# SW.net
KiCad netlist of a schematic drawn in Altium Designer
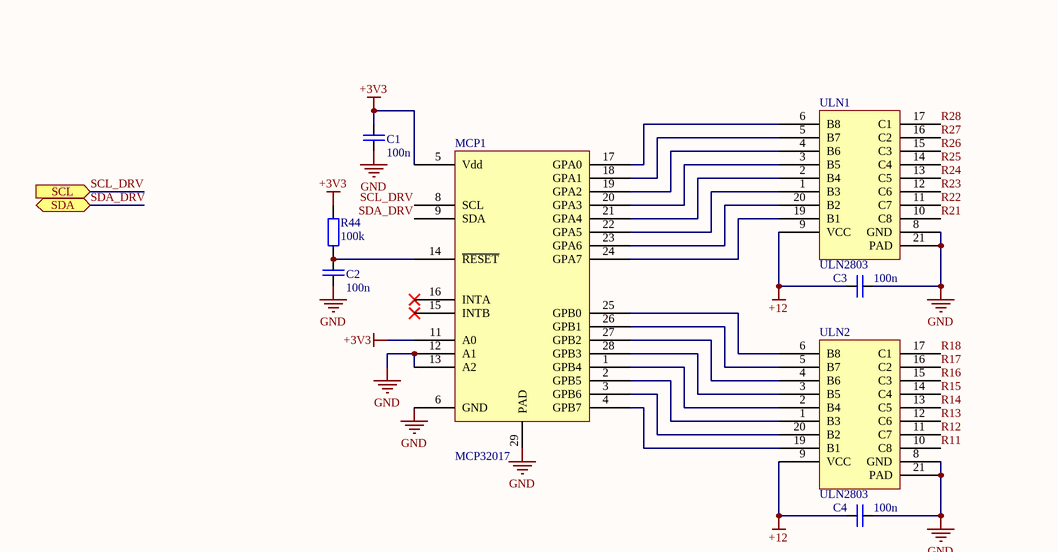
[diagram p0: SW.SchDoc, top left]
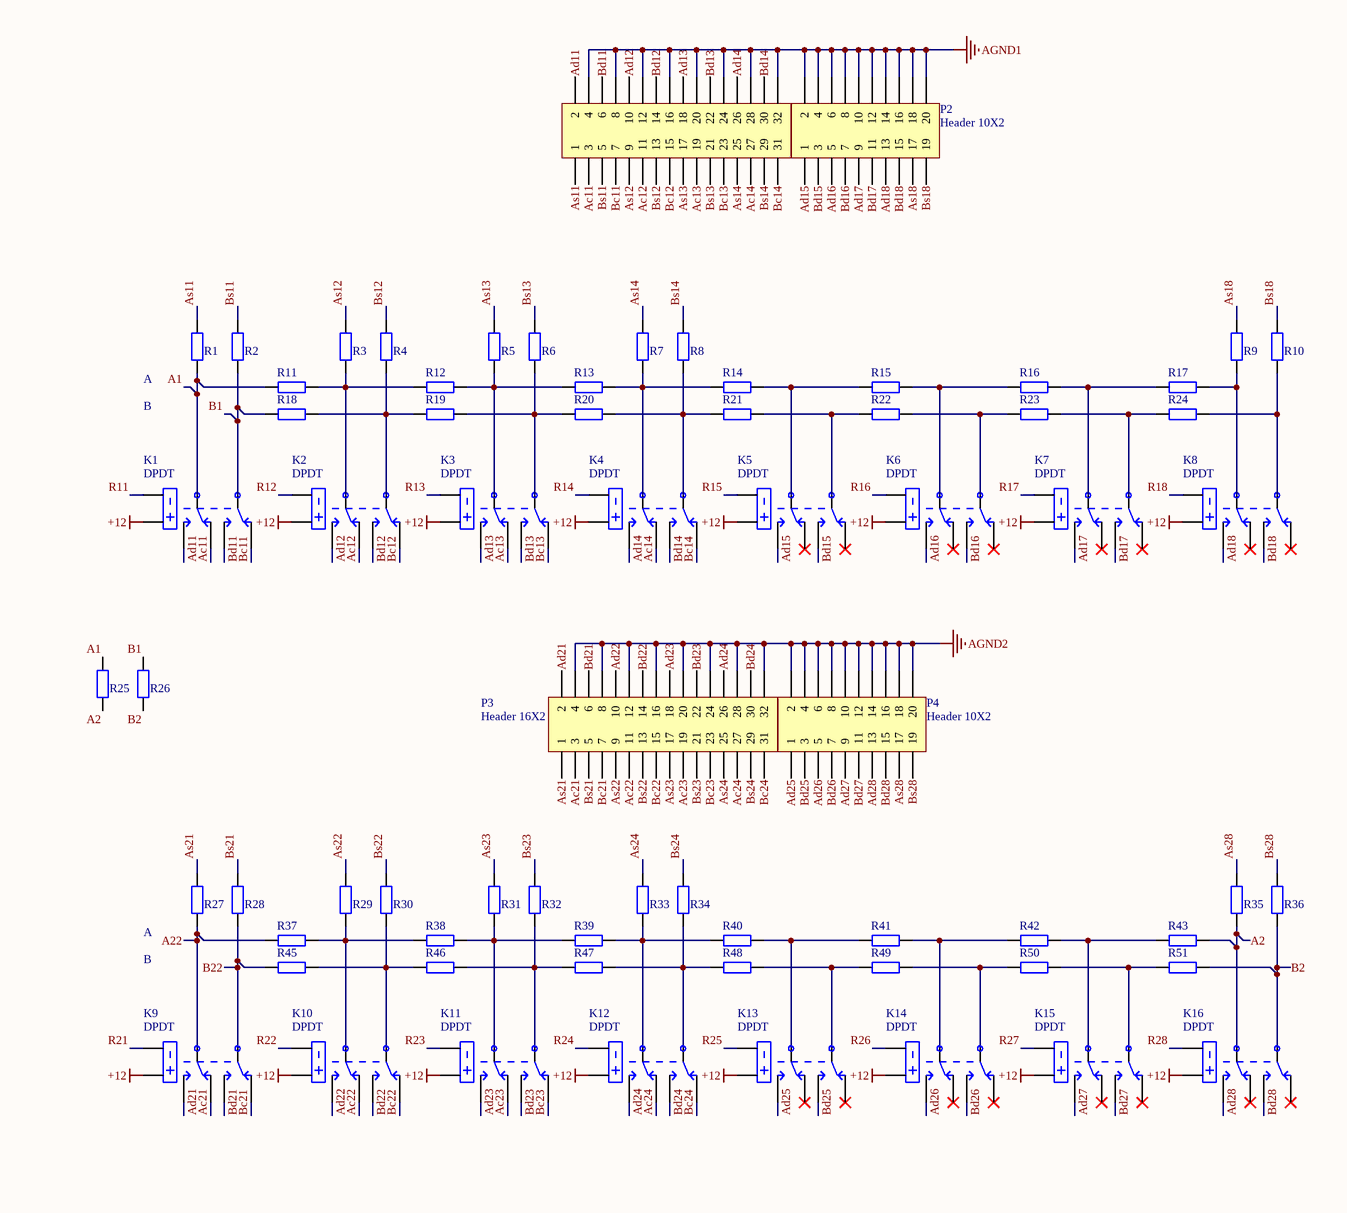
[diagram p1: SW.SchDoc, top right]
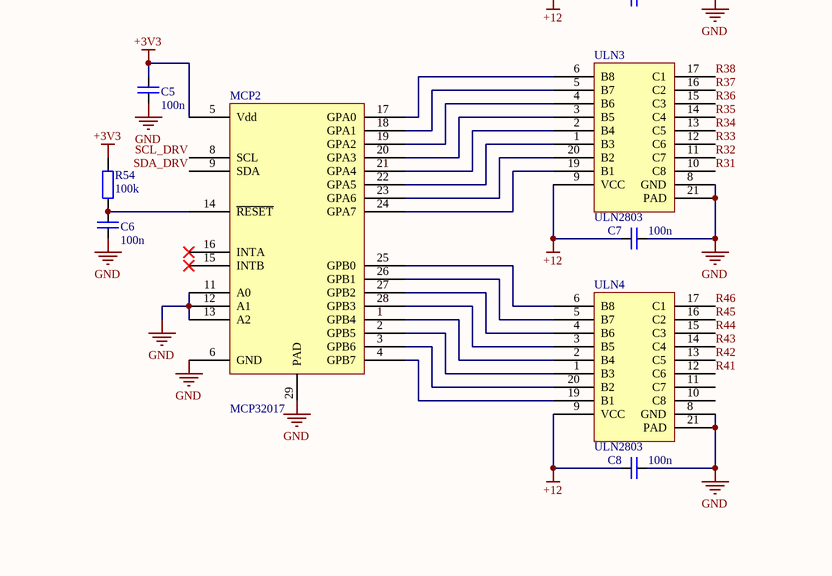
[diagram p2: SW.SchDoc, bottom left]
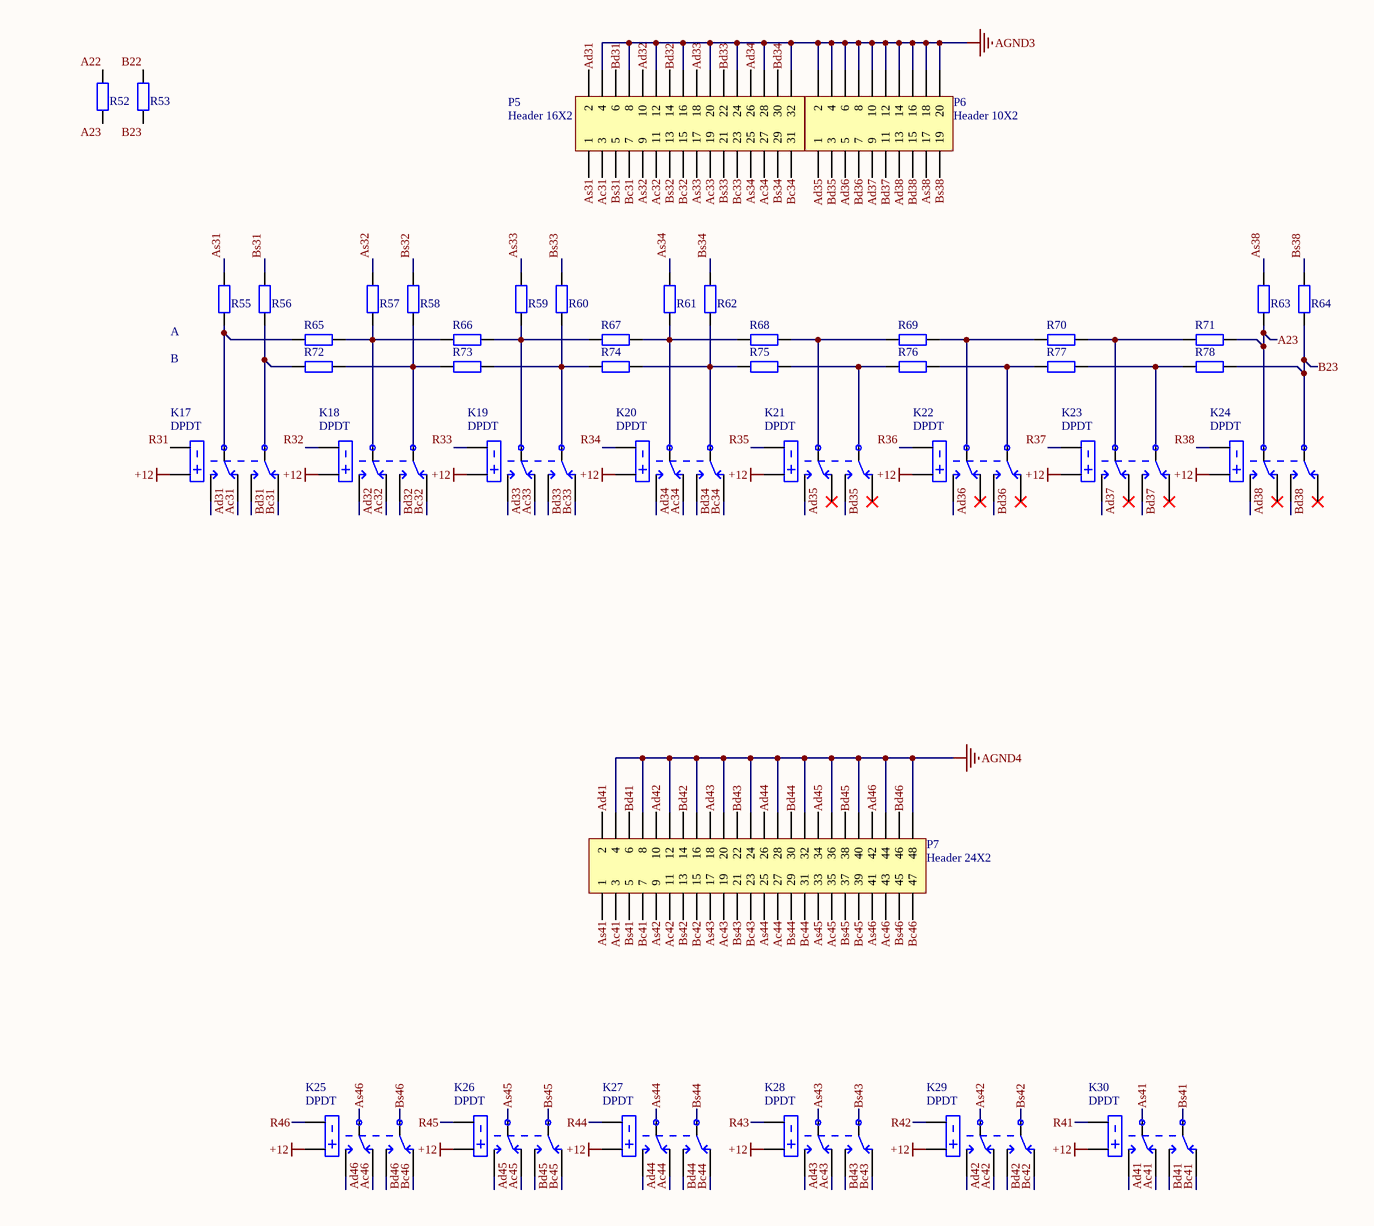
[diagram p3: SW.SchDoc, bottom right]

(export (version "E")
  (design (tool "Eeschema 10.0.6"))
  (components
    (comp (ref "C1")
      (value "100n")
      (footprint "R1005_0402i_L")
      (description "Capacitor")
      (libsource (lib "General") (part "C"))
    )
    (comp (ref "C2")
      (value "100n")
      (footprint "R1005_0402i_L")
      (description "Capacitor")
      (libsource (lib "General") (part "C"))
    )
    (comp (ref "C3")
      (value "100n")
      (footprint "R1005_0402i_L")
      (description "Capacitor")
      (libsource (lib "General") (part "C"))
    )
    (comp (ref "C4")
      (value "100n")
      (footprint "R1005_0402i_L")
      (description "Capacitor")
      (libsource (lib "General") (part "C"))
    )
    (comp (ref "C5")
      (value "100n")
      (footprint "R1005_0402i_L")
      (description "Capacitor")
      (libsource (lib "General") (part "C"))
    )
    (comp (ref "C6")
      (value "100n")
      (footprint "R1005_0402i_L")
      (description "Capacitor")
      (libsource (lib "General") (part "C"))
    )
    (comp (ref "C7")
      (value "100n")
      (footprint "R1005_0402i_L")
      (description "Capacitor")
      (libsource (lib "General") (part "C"))
    )
    (comp (ref "C8")
      (value "100n")
      (footprint "R1005_0402i_L")
      (description "Capacitor")
      (libsource (lib "General") (part "C"))
    )
    (comp (ref "K1")
      (value "DPDT")
      (footprint "AXICOM IM-G Relay")
      (description "TE CONNECTIVITY  IM-GR  RELAY, DPDT, NO")
      (libsource (lib "components_library") (part "IM-GR Relay DPDT"))
    )
    (comp (ref "K2")
      (value "DPDT")
      (footprint "AXICOM IM-G Relay")
      (description "TE CONNECTIVITY  IM-GR  RELAY, DPDT, NO")
      (libsource (lib "components_library") (part "IM-GR Relay DPDT"))
    )
    (comp (ref "K3")
      (value "DPDT")
      (footprint "AXICOM IM-G Relay")
      (description "TE CONNECTIVITY  IM-GR  RELAY, DPDT, NO")
      (libsource (lib "components_library") (part "IM-GR Relay DPDT"))
    )
    (comp (ref "K4")
      (value "DPDT")
      (footprint "AXICOM IM-G Relay")
      (description "TE CONNECTIVITY  IM-GR  RELAY, DPDT, NO")
      (libsource (lib "components_library") (part "IM-GR Relay DPDT"))
    )
    (comp (ref "K5")
      (value "DPDT")
      (footprint "AXICOM IM-G Relay")
      (description "TE CONNECTIVITY  IM-GR  RELAY, DPDT, NO")
      (libsource (lib "components_library") (part "IM-GR Relay DPDT"))
    )
    (comp (ref "K6")
      (value "DPDT")
      (footprint "AXICOM IM-G Relay")
      (description "TE CONNECTIVITY  IM-GR  RELAY, DPDT, NO")
      (libsource (lib "components_library") (part "IM-GR Relay DPDT"))
    )
    (comp (ref "K7")
      (value "DPDT")
      (footprint "AXICOM IM-G Relay")
      (description "TE CONNECTIVITY  IM-GR  RELAY, DPDT, NO")
      (libsource (lib "components_library") (part "IM-GR Relay DPDT"))
    )
    (comp (ref "K8")
      (value "DPDT")
      (footprint "AXICOM IM-G Relay")
      (description "TE CONNECTIVITY  IM-GR  RELAY, DPDT, NO")
      (libsource (lib "components_library") (part "IM-GR Relay DPDT"))
    )
    (comp (ref "K9")
      (value "DPDT")
      (footprint "AXICOM IM-G Relay")
      (description "TE CONNECTIVITY  IM-GR  RELAY, DPDT, NO")
      (libsource (lib "components_library") (part "IM-GR Relay DPDT"))
    )
    (comp (ref "K10")
      (value "DPDT")
      (footprint "AXICOM IM-G Relay")
      (description "TE CONNECTIVITY  IM-GR  RELAY, DPDT, NO")
      (libsource (lib "components_library") (part "IM-GR Relay DPDT"))
    )
    (comp (ref "K11")
      (value "DPDT")
      (footprint "AXICOM IM-G Relay")
      (description "TE CONNECTIVITY  IM-GR  RELAY, DPDT, NO")
      (libsource (lib "components_library") (part "IM-GR Relay DPDT"))
    )
    (comp (ref "K12")
      (value "DPDT")
      (footprint "AXICOM IM-G Relay")
      (description "TE CONNECTIVITY  IM-GR  RELAY, DPDT, NO")
      (libsource (lib "components_library") (part "IM-GR Relay DPDT"))
    )
    (comp (ref "K13")
      (value "DPDT")
      (footprint "AXICOM IM-G Relay")
      (description "TE CONNECTIVITY  IM-GR  RELAY, DPDT, NO")
      (libsource (lib "components_library") (part "IM-GR Relay DPDT"))
    )
    (comp (ref "K14")
      (value "DPDT")
      (footprint "AXICOM IM-G Relay")
      (description "TE CONNECTIVITY  IM-GR  RELAY, DPDT, NO")
      (libsource (lib "components_library") (part "IM-GR Relay DPDT"))
    )
    (comp (ref "K15")
      (value "DPDT")
      (footprint "AXICOM IM-G Relay")
      (description "TE CONNECTIVITY  IM-GR  RELAY, DPDT, NO")
      (libsource (lib "components_library") (part "IM-GR Relay DPDT"))
    )
    (comp (ref "K16")
      (value "DPDT")
      (footprint "AXICOM IM-G Relay")
      (description "TE CONNECTIVITY  IM-GR  RELAY, DPDT, NO")
      (libsource (lib "components_library") (part "IM-GR Relay DPDT"))
    )
    (comp (ref "K17")
      (value "DPDT")
      (footprint "AXICOM IM-G Relay")
      (description "TE CONNECTIVITY  IM-GR  RELAY, DPDT, NO")
      (libsource (lib "components_library") (part "IM-GR Relay DPDT"))
    )
    (comp (ref "K18")
      (value "DPDT")
      (footprint "AXICOM IM-G Relay")
      (description "TE CONNECTIVITY  IM-GR  RELAY, DPDT, NO")
      (libsource (lib "components_library") (part "IM-GR Relay DPDT"))
    )
    (comp (ref "K19")
      (value "DPDT")
      (footprint "AXICOM IM-G Relay")
      (description "TE CONNECTIVITY  IM-GR  RELAY, DPDT, NO")
      (libsource (lib "components_library") (part "IM-GR Relay DPDT"))
    )
    (comp (ref "K20")
      (value "DPDT")
      (footprint "AXICOM IM-G Relay")
      (description "TE CONNECTIVITY  IM-GR  RELAY, DPDT, NO")
      (libsource (lib "components_library") (part "IM-GR Relay DPDT"))
    )
    (comp (ref "K21")
      (value "DPDT")
      (footprint "AXICOM IM-G Relay")
      (description "TE CONNECTIVITY  IM-GR  RELAY, DPDT, NO")
      (libsource (lib "components_library") (part "IM-GR Relay DPDT"))
    )
    (comp (ref "K22")
      (value "DPDT")
      (footprint "AXICOM IM-G Relay")
      (description "TE CONNECTIVITY  IM-GR  RELAY, DPDT, NO")
      (libsource (lib "components_library") (part "IM-GR Relay DPDT"))
    )
    (comp (ref "K23")
      (value "DPDT")
      (footprint "AXICOM IM-G Relay")
      (description "TE CONNECTIVITY  IM-GR  RELAY, DPDT, NO")
      (libsource (lib "components_library") (part "IM-GR Relay DPDT"))
    )
    (comp (ref "K24")
      (value "DPDT")
      (footprint "AXICOM IM-G Relay")
      (description "TE CONNECTIVITY  IM-GR  RELAY, DPDT, NO")
      (libsource (lib "components_library") (part "IM-GR Relay DPDT"))
    )
    (comp (ref "K25")
      (value "DPDT")
      (footprint "AXICOM IM-G Relay")
      (description "TE CONNECTIVITY  IM-GR  RELAY, DPDT, NO")
      (libsource (lib "components_library") (part "IM-GR Relay DPDT"))
    )
    (comp (ref "K26")
      (value "DPDT")
      (footprint "AXICOM IM-G Relay")
      (description "TE CONNECTIVITY  IM-GR  RELAY, DPDT, NO")
      (libsource (lib "components_library") (part "IM-GR Relay DPDT"))
    )
    (comp (ref "K27")
      (value "DPDT")
      (footprint "AXICOM IM-G Relay")
      (description "TE CONNECTIVITY  IM-GR  RELAY, DPDT, NO")
      (libsource (lib "components_library") (part "IM-GR Relay DPDT"))
    )
    (comp (ref "K28")
      (value "DPDT")
      (footprint "AXICOM IM-G Relay")
      (description "TE CONNECTIVITY  IM-GR  RELAY, DPDT, NO")
      (libsource (lib "components_library") (part "IM-GR Relay DPDT"))
    )
    (comp (ref "K29")
      (value "DPDT")
      (footprint "AXICOM IM-G Relay")
      (description "TE CONNECTIVITY  IM-GR  RELAY, DPDT, NO")
      (libsource (lib "components_library") (part "IM-GR Relay DPDT"))
    )
    (comp (ref "K30")
      (value "DPDT")
      (footprint "AXICOM IM-G Relay")
      (description "TE CONNECTIVITY  IM-GR  RELAY, DPDT, NO")
      (libsource (lib "components_library") (part "IM-GR Relay DPDT"))
    )
    (comp (ref "MCP1")
      (value "MCP32017")
      (footprint "MCP23017 QFN")
      (libsource (lib "components_library") (part "MCP32017"))
    )
    (comp (ref "MCP2")
      (value "MCP32017")
      (footprint "MCP23017 QFN")
      (libsource (lib "components_library") (part "MCP32017"))
    )
    (comp (ref "P1")
      (value "Header 16X2")
      (footprint "HDR2X16")
      (description "Header, 16-Pin, Dual row")
      (fields (field (name "PUBLISHER") "Altium Limited"))
      (libsource (lib "Miscellaneous Connectors") (part "Header 16X2"))
    )
    (comp (ref "P2")
      (value "Header 10X2")
      (footprint "HDR2X10")
      (description "Header, 10-Pin, Dual row")
      (fields (field (name "PUBLISHER") "Altium Limited"))
      (libsource (lib "Miscellaneous Connectors") (part "Header 10X2"))
    )
    (comp (ref "P3")
      (value "Header 16X2")
      (footprint "HDR2X16")
      (description "Header, 16-Pin, Dual row")
      (fields (field (name "PUBLISHER") "Altium Limited"))
      (libsource (lib "Miscellaneous Connectors") (part "Header 16X2"))
    )
    (comp (ref "P4")
      (value "Header 10X2")
      (footprint "HDR2X10")
      (description "Header, 10-Pin, Dual row")
      (fields (field (name "PUBLISHER") "Altium Limited"))
      (libsource (lib "Miscellaneous Connectors") (part "Header 10X2"))
    )
    (comp (ref "P5")
      (value "Header 16X2")
      (footprint "HDR2X16")
      (description "Header, 16-Pin, Dual row")
      (fields (field (name "PUBLISHER") "Altium Limited"))
      (libsource (lib "Miscellaneous Connectors") (part "Header 16X2"))
    )
    (comp (ref "P6")
      (value "Header 10X2")
      (footprint "HDR2X10")
      (description "Header, 10-Pin, Dual row")
      (fields (field (name "PUBLISHER") "Altium Limited"))
      (libsource (lib "Miscellaneous Connectors") (part "Header 10X2"))
    )
    (comp (ref "P7")
      (value "Header 24X2")
      (footprint "HDR2X24")
      (description "Header, 24-Pin, Dual row")
      (fields (field (name "PUBLISHER") "Altium Limited"))
      (libsource (lib "Miscellaneous Connectors") (part "Header 24X2"))
    )
    (comp (ref "R1") (value "R") (footprint "R1608_0603I_L") (libsource (lib "General") (part "R")))
    (comp (ref "R2") (value "R") (footprint "R1608_0603I_L") (libsource (lib "General") (part "R")))
    (comp (ref "R3") (value "R") (footprint "R1608_0603I_L") (libsource (lib "General") (part "R")))
    (comp (ref "R4") (value "R") (footprint "R1608_0603I_L") (libsource (lib "General") (part "R")))
    (comp (ref "R5") (value "R") (footprint "R1608_0603I_L") (libsource (lib "General") (part "R")))
    (comp (ref "R6") (value "R") (footprint "R1608_0603I_L") (libsource (lib "General") (part "R")))
    (comp (ref "R7") (value "R") (footprint "R1608_0603I_L") (libsource (lib "General") (part "R")))
    (comp (ref "R8") (value "R") (footprint "R1608_0603I_L") (libsource (lib "General") (part "R")))
    (comp (ref "R9") (value "R") (footprint "R1608_0603I_L") (libsource (lib "General") (part "R")))
    (comp (ref "R10") (value "R") (footprint "R1608_0603I_L") (libsource (lib "General") (part "R")))
    (comp (ref "R11") (value "R") (footprint "R1608_0603I_L") (libsource (lib "General") (part "R")))
    (comp (ref "R12") (value "R") (footprint "R1608_0603I_L") (libsource (lib "General") (part "R")))
    (comp (ref "R13") (value "R") (footprint "R1608_0603I_L") (libsource (lib "General") (part "R")))
    (comp (ref "R14") (value "R") (footprint "R1608_0603I_L") (libsource (lib "General") (part "R")))
    (comp (ref "R15") (value "R") (footprint "R1608_0603I_L") (libsource (lib "General") (part "R")))
    (comp (ref "R16") (value "R") (footprint "R1608_0603I_L") (libsource (lib "General") (part "R")))
    (comp (ref "R17") (value "R") (footprint "R1608_0603I_L") (libsource (lib "General") (part "R")))
    (comp (ref "R18") (value "R") (footprint "R1608_0603I_L") (libsource (lib "General") (part "R")))
    (comp (ref "R19") (value "R") (footprint "R1608_0603I_L") (libsource (lib "General") (part "R")))
    (comp (ref "R20") (value "R") (footprint "R1608_0603I_L") (libsource (lib "General") (part "R")))
    (comp (ref "R21") (value "R") (footprint "R1608_0603I_L") (libsource (lib "General") (part "R")))
    (comp (ref "R22") (value "R") (footprint "R1608_0603I_L") (libsource (lib "General") (part "R")))
    (comp (ref "R23") (value "R") (footprint "R1608_0603I_L") (libsource (lib "General") (part "R")))
    (comp (ref "R24") (value "R") (footprint "R1608_0603I_L") (libsource (lib "General") (part "R")))
    (comp (ref "R25") (value "R") (footprint "R1608_0603I_L") (libsource (lib "General") (part "R")))
    (comp (ref "R26") (value "R") (footprint "R1608_0603I_L") (libsource (lib "General") (part "R")))
    (comp (ref "R27") (value "R") (footprint "R1608_0603I_L") (libsource (lib "General") (part "R")))
    (comp (ref "R28") (value "R") (footprint "R1608_0603I_L") (libsource (lib "General") (part "R")))
    (comp (ref "R29") (value "R") (footprint "R1608_0603I_L") (libsource (lib "General") (part "R")))
    (comp (ref "R30") (value "R") (footprint "R1608_0603I_L") (libsource (lib "General") (part "R")))
    (comp (ref "R31") (value "R") (footprint "R1608_0603I_L") (libsource (lib "General") (part "R")))
    (comp (ref "R32") (value "R") (footprint "R1608_0603I_L") (libsource (lib "General") (part "R")))
    (comp (ref "R33") (value "R") (footprint "R1608_0603I_L") (libsource (lib "General") (part "R")))
    (comp (ref "R34") (value "R") (footprint "R1608_0603I_L") (libsource (lib "General") (part "R")))
    (comp (ref "R35") (value "R") (footprint "R1608_0603I_L") (libsource (lib "General") (part "R")))
    (comp (ref "R36") (value "R") (footprint "R1608_0603I_L") (libsource (lib "General") (part "R")))
    (comp (ref "R37") (value "R") (footprint "R1608_0603I_L") (libsource (lib "General") (part "R")))
    (comp (ref "R38") (value "R") (footprint "R1608_0603I_L") (libsource (lib "General") (part "R")))
    (comp (ref "R39") (value "R") (footprint "R1608_0603I_L") (libsource (lib "General") (part "R")))
    (comp (ref "R40") (value "R") (footprint "R1608_0603I_L") (libsource (lib "General") (part "R")))
    (comp (ref "R41") (value "R") (footprint "R1608_0603I_L") (libsource (lib "General") (part "R")))
    (comp (ref "R42") (value "R") (footprint "R1608_0603I_L") (libsource (lib "General") (part "R")))
    (comp (ref "R43") (value "R") (footprint "R1608_0603I_L") (libsource (lib "General") (part "R")))
    (comp (ref "R44")
      (value "100k")
      (footprint "R1005_0402i_L")
      (description "R")
      (libsource (lib "General") (part "R"))
    )
    (comp (ref "R45") (value "R") (footprint "R1608_0603I_L") (libsource (lib "General") (part "R")))
    (comp (ref "R46") (value "R") (footprint "R1608_0603I_L") (libsource (lib "General") (part "R")))
    (comp (ref "R47") (value "R") (footprint "R1608_0603I_L") (libsource (lib "General") (part "R")))
    (comp (ref "R48") (value "R") (footprint "R1608_0603I_L") (libsource (lib "General") (part "R")))
    (comp (ref "R49") (value "R") (footprint "R1608_0603I_L") (libsource (lib "General") (part "R")))
    (comp (ref "R50") (value "R") (footprint "R1608_0603I_L") (libsource (lib "General") (part "R")))
    (comp (ref "R51") (value "R") (footprint "R1608_0603I_L") (libsource (lib "General") (part "R")))
    (comp (ref "R52") (value "R") (footprint "R1608_0603I_L") (libsource (lib "General") (part "R")))
    (comp (ref "R53") (value "R") (footprint "R1608_0603I_L") (libsource (lib "General") (part "R")))
    (comp (ref "R54")
      (value "100k")
      (footprint "R1005_0402i_L")
      (description "R")
      (libsource (lib "General") (part "R"))
    )
    (comp (ref "R55") (value "R") (footprint "R1608_0603I_L") (libsource (lib "General") (part "R")))
    (comp (ref "R56") (value "R") (footprint "R1608_0603I_L") (libsource (lib "General") (part "R")))
    (comp (ref "R57") (value "R") (footprint "R1608_0603I_L") (libsource (lib "General") (part "R")))
    (comp (ref "R58") (value "R") (footprint "R1608_0603I_L") (libsource (lib "General") (part "R")))
    (comp (ref "R59") (value "R") (footprint "R1608_0603I_L") (libsource (lib "General") (part "R")))
    (comp (ref "R60") (value "R") (footprint "R1608_0603I_L") (libsource (lib "General") (part "R")))
    (comp (ref "R61") (value "R") (footprint "R1608_0603I_L") (libsource (lib "General") (part "R")))
    (comp (ref "R62") (value "R") (footprint "R1608_0603I_L") (libsource (lib "General") (part "R")))
    (comp (ref "R63") (value "R") (footprint "R1608_0603I_L") (libsource (lib "General") (part "R")))
    (comp (ref "R64") (value "R") (footprint "R1608_0603I_L") (libsource (lib "General") (part "R")))
    (comp (ref "R65") (value "R") (footprint "R1608_0603I_L") (libsource (lib "General") (part "R")))
    (comp (ref "R66") (value "R") (footprint "R1608_0603I_L") (libsource (lib "General") (part "R")))
    (comp (ref "R67") (value "R") (footprint "R1608_0603I_L") (libsource (lib "General") (part "R")))
    (comp (ref "R68") (value "R") (footprint "R1608_0603I_L") (libsource (lib "General") (part "R")))
    (comp (ref "R69") (value "R") (footprint "R1608_0603I_L") (libsource (lib "General") (part "R")))
    (comp (ref "R70") (value "R") (footprint "R1608_0603I_L") (libsource (lib "General") (part "R")))
    (comp (ref "R71") (value "R") (footprint "R1608_0603I_L") (libsource (lib "General") (part "R")))
    (comp (ref "R72") (value "R") (footprint "R1608_0603I_L") (libsource (lib "General") (part "R")))
    (comp (ref "R73") (value "R") (footprint "R1608_0603I_L") (libsource (lib "General") (part "R")))
    (comp (ref "R74") (value "R") (footprint "R1608_0603I_L") (libsource (lib "General") (part "R")))
    (comp (ref "R75") (value "R") (footprint "R1608_0603I_L") (libsource (lib "General") (part "R")))
    (comp (ref "R76") (value "R") (footprint "R1608_0603I_L") (libsource (lib "General") (part "R")))
    (comp (ref "R77") (value "R") (footprint "R1608_0603I_L") (libsource (lib "General") (part "R")))
    (comp (ref "R78") (value "R") (footprint "R1608_0603I_L") (libsource (lib "General") (part "R")))
    (comp (ref "ULN1")
      (value "ULN2803")
      (footprint "QFN127P600-8N")
      (libsource (lib "Schlib1") (part "ULN2803"))
    )
    (comp (ref "ULN2")
      (value "ULN2803")
      (footprint "QFN127P600-8N")
      (libsource (lib "Schlib1") (part "ULN2803"))
    )
    (comp (ref "ULN3")
      (value "ULN2803")
      (footprint "QFN127P600-8N")
      (libsource (lib "Schlib1") (part "ULN2803"))
    )
    (comp (ref "ULN4")
      (value "ULN2803")
      (footprint "QFN127P600-8N")
      (libsource (lib "Schlib1") (part "ULN2803"))
    )
  )
  (nets
    (net (code "1") (name "+3V3") (class "Default")
      (node (ref "C1") (pin "2") (pinfunction "2_2") (pintype "passive"))
      (node (ref "C5") (pin "2") (pinfunction "2_2") (pintype "passive"))
      (node (ref "MCP1") (pin "11") (pinfunction "A0_11") (pintype "passive"))
      (node (ref "MCP1") (pin "5") (pinfunction "Vdd_5") (pintype "passive"))
      (node (ref "MCP2") (pin "5") (pinfunction "Vdd_5") (pintype "passive"))
      (node (ref "R44") (pin "1") (pintype "passive"))
      (node (ref "R54") (pin "1") (pintype "passive"))
    )
    (net (code "2") (name "+12") (class "Default")
      (node (ref "C3") (pin "1") (pinfunction "1_1") (pintype "passive"))
      (node (ref "C4") (pin "1") (pinfunction "1_1") (pintype "passive"))
      (node (ref "C7") (pin "1") (pinfunction "1_1") (pintype "passive"))
      (node (ref "C8") (pin "1") (pinfunction "1_1") (pintype "passive"))
      (node (ref "K1") (pin "1") (pinfunction "1_1") (pintype "passive"))
      (node (ref "K10") (pin "1") (pinfunction "1_1") (pintype "passive"))
      (node (ref "K11") (pin "1") (pinfunction "1_1") (pintype "passive"))
      (node (ref "K12") (pin "1") (pinfunction "1_1") (pintype "passive"))
      (node (ref "K13") (pin "1") (pinfunction "1_1") (pintype "passive"))
      (node (ref "K14") (pin "1") (pinfunction "1_1") (pintype "passive"))
      (node (ref "K15") (pin "1") (pinfunction "1_1") (pintype "passive"))
      (node (ref "K16") (pin "1") (pinfunction "1_1") (pintype "passive"))
      (node (ref "K17") (pin "1") (pinfunction "1_1") (pintype "passive"))
      (node (ref "K18") (pin "1") (pinfunction "1_1") (pintype "passive"))
      (node (ref "K19") (pin "1") (pinfunction "1_1") (pintype "passive"))
      (node (ref "K2") (pin "1") (pinfunction "1_1") (pintype "passive"))
      (node (ref "K20") (pin "1") (pinfunction "1_1") (pintype "passive"))
      (node (ref "K21") (pin "1") (pinfunction "1_1") (pintype "passive"))
      (node (ref "K22") (pin "1") (pinfunction "1_1") (pintype "passive"))
      (node (ref "K23") (pin "1") (pinfunction "1_1") (pintype "passive"))
      (node (ref "K24") (pin "1") (pinfunction "1_1") (pintype "passive"))
      (node (ref "K25") (pin "1") (pinfunction "1_1") (pintype "passive"))
      (node (ref "K26") (pin "1") (pinfunction "1_1") (pintype "passive"))
      (node (ref "K27") (pin "1") (pinfunction "1_1") (pintype "passive"))
      (node (ref "K28") (pin "1") (pinfunction "1_1") (pintype "passive"))
      (node (ref "K29") (pin "1") (pinfunction "1_1") (pintype "passive"))
      (node (ref "K3") (pin "1") (pinfunction "1_1") (pintype "passive"))
      (node (ref "K30") (pin "1") (pinfunction "1_1") (pintype "passive"))
      (node (ref "K4") (pin "1") (pinfunction "1_1") (pintype "passive"))
      (node (ref "K5") (pin "1") (pinfunction "1_1") (pintype "passive"))
      (node (ref "K6") (pin "1") (pinfunction "1_1") (pintype "passive"))
      (node (ref "K7") (pin "1") (pinfunction "1_1") (pintype "passive"))
      (node (ref "K8") (pin "1") (pinfunction "1_1") (pintype "passive"))
      (node (ref "K9") (pin "1") (pinfunction "1_1") (pintype "passive"))
      (node (ref "ULN1") (pin "9") (pinfunction "VCC_9") (pintype "passive"))
      (node (ref "ULN2") (pin "9") (pinfunction "VCC_9") (pintype "passive"))
      (node (ref "ULN3") (pin "9") (pinfunction "VCC_9") (pintype "passive"))
      (node (ref "ULN4") (pin "9") (pinfunction "VCC_9") (pintype "passive"))
    )
    (net (code "3") (name "/A1") (class "Default")
      (node (ref "K1") (pin "3") (pinfunction "3_3") (pintype "passive"))
      (node (ref "R1") (pin "1") (pintype "passive"))
      (node (ref "R11") (pin "1") (pintype "passive"))
      (node (ref "R25") (pin "2") (pintype "passive"))
    )
    (net (code "4") (name "/A2") (class "Default")
      (node (ref "K16") (pin "3") (pinfunction "3_3") (pintype "passive"))
      (node (ref "R25") (pin "1") (pintype "passive"))
      (node (ref "R35") (pin "1") (pintype "passive"))
      (node (ref "R43") (pin "2") (pintype "passive"))
    )
    (net (code "5") (name "/A22") (class "Default")
      (node (ref "K9") (pin "3") (pinfunction "3_3") (pintype "passive"))
      (node (ref "R27") (pin "1") (pintype "passive"))
      (node (ref "R37") (pin "1") (pintype "passive"))
      (node (ref "R52") (pin "2") (pintype "passive"))
    )
    (net (code "6") (name "/A23") (class "Default")
      (node (ref "K24") (pin "3") (pinfunction "3_3") (pintype "passive"))
      (node (ref "R52") (pin "1") (pintype "passive"))
      (node (ref "R63") (pin "1") (pintype "passive"))
      (node (ref "R71") (pin "2") (pintype "passive"))
    )
    (net (code "7") (name "/Ac11") (class "Default")
      (node (ref "K1") (pin "2") (pinfunction "2_2") (pintype "passive"))
      (node (ref "P1") (pin "3") (pinfunction "3_3") (pintype "passive"))
    )
    (net (code "8") (name "/Ac12") (class "Default")
      (node (ref "K2") (pin "2") (pinfunction "2_2") (pintype "passive"))
      (node (ref "P1") (pin "11") (pinfunction "11_11") (pintype "passive"))
    )
    (net (code "9") (name "/Ac13") (class "Default")
      (node (ref "K3") (pin "2") (pinfunction "2_2") (pintype "passive"))
      (node (ref "P1") (pin "19") (pinfunction "19_19") (pintype "passive"))
    )
    (net (code "10") (name "/Ac14") (class "Default")
      (node (ref "K4") (pin "2") (pinfunction "2_2") (pintype "passive"))
      (node (ref "P1") (pin "27") (pinfunction "27_27") (pintype "passive"))
    )
    (net (code "11") (name "/Ac21") (class "Default")
      (node (ref "K9") (pin "2") (pinfunction "2_2") (pintype "passive"))
      (node (ref "P3") (pin "3") (pinfunction "3_3") (pintype "passive"))
    )
    (net (code "12") (name "/Ac22") (class "Default")
      (node (ref "K10") (pin "2") (pinfunction "2_2") (pintype "passive"))
      (node (ref "P3") (pin "11") (pinfunction "11_11") (pintype "passive"))
    )
    (net (code "13") (name "/Ac23") (class "Default")
      (node (ref "K11") (pin "2") (pinfunction "2_2") (pintype "passive"))
      (node (ref "P3") (pin "19") (pinfunction "19_19") (pintype "passive"))
    )
    (net (code "14") (name "/Ac24") (class "Default")
      (node (ref "K12") (pin "2") (pinfunction "2_2") (pintype "passive"))
      (node (ref "P3") (pin "27") (pinfunction "27_27") (pintype "passive"))
    )
    (net (code "15") (name "/Ac31") (class "Default")
      (node (ref "K17") (pin "2") (pinfunction "2_2") (pintype "passive"))
      (node (ref "P5") (pin "3") (pinfunction "3_3") (pintype "passive"))
    )
    (net (code "16") (name "/Ac32") (class "Default")
      (node (ref "K18") (pin "2") (pinfunction "2_2") (pintype "passive"))
      (node (ref "P5") (pin "11") (pinfunction "11_11") (pintype "passive"))
    )
    (net (code "17") (name "/Ac33") (class "Default")
      (node (ref "K19") (pin "2") (pinfunction "2_2") (pintype "passive"))
      (node (ref "P5") (pin "19") (pinfunction "19_19") (pintype "passive"))
    )
    (net (code "18") (name "/Ac34") (class "Default")
      (node (ref "K20") (pin "2") (pinfunction "2_2") (pintype "passive"))
      (node (ref "P5") (pin "27") (pinfunction "27_27") (pintype "passive"))
    )
    (net (code "19") (name "/Ac41") (class "Default")
      (node (ref "K30") (pin "2") (pinfunction "2_2") (pintype "passive"))
      (node (ref "P7") (pin "3") (pinfunction "3_3") (pintype "passive"))
    )
    (net (code "20") (name "/Ac42") (class "Default")
      (node (ref "K29") (pin "2") (pinfunction "2_2") (pintype "passive"))
      (node (ref "P7") (pin "11") (pinfunction "11_11") (pintype "passive"))
    )
    (net (code "21") (name "/Ac43") (class "Default")
      (node (ref "K28") (pin "2") (pinfunction "2_2") (pintype "passive"))
      (node (ref "P7") (pin "19") (pinfunction "19_19") (pintype "passive"))
    )
    (net (code "22") (name "/Ac44") (class "Default")
      (node (ref "K27") (pin "2") (pinfunction "2_2") (pintype "passive"))
      (node (ref "P7") (pin "27") (pinfunction "27_27") (pintype "passive"))
    )
    (net (code "23") (name "/Ac45") (class "Default")
      (node (ref "K26") (pin "2") (pinfunction "2_2") (pintype "passive"))
      (node (ref "P7") (pin "35") (pinfunction "35_35") (pintype "passive"))
    )
    (net (code "24") (name "/Ac46") (class "Default")
      (node (ref "K25") (pin "2") (pinfunction "2_2") (pintype "passive"))
      (node (ref "P7") (pin "43") (pinfunction "43_43") (pintype "passive"))
    )
    (net (code "25") (name "/Ad11") (class "Default")
      (node (ref "K1") (pin "4") (pinfunction "4_4") (pintype "passive"))
      (node (ref "P1") (pin "2") (pinfunction "2_2") (pintype "passive"))
    )
    (net (code "26") (name "/Ad12") (class "Default")
      (node (ref "K2") (pin "4") (pinfunction "4_4") (pintype "passive"))
      (node (ref "P1") (pin "10") (pinfunction "10_10") (pintype "passive"))
    )
    (net (code "27") (name "/Ad13") (class "Default")
      (node (ref "K3") (pin "4") (pinfunction "4_4") (pintype "passive"))
      (node (ref "P1") (pin "18") (pinfunction "18_18") (pintype "passive"))
    )
    (net (code "28") (name "/Ad14") (class "Default")
      (node (ref "K4") (pin "4") (pinfunction "4_4") (pintype "passive"))
      (node (ref "P1") (pin "26") (pinfunction "26_26") (pintype "passive"))
    )
    (net (code "29") (name "/Ad15") (class "Default")
      (node (ref "K5") (pin "4") (pinfunction "4_4") (pintype "passive"))
      (node (ref "P2") (pin "1") (pinfunction "1_1") (pintype "passive"))
    )
    (net (code "30") (name "/Ad16") (class "Default")
      (node (ref "K6") (pin "4") (pinfunction "4_4") (pintype "passive"))
      (node (ref "P2") (pin "5") (pinfunction "5_5") (pintype "passive"))
    )
    (net (code "31") (name "/Ad17") (class "Default")
      (node (ref "K7") (pin "4") (pinfunction "4_4") (pintype "passive"))
      (node (ref "P2") (pin "9") (pinfunction "9_9") (pintype "passive"))
    )
    (net (code "32") (name "/Ad18") (class "Default")
      (node (ref "K8") (pin "4") (pinfunction "4_4") (pintype "passive"))
      (node (ref "P2") (pin "13") (pinfunction "13_13") (pintype "passive"))
    )
    (net (code "33") (name "/Ad21") (class "Default")
      (node (ref "K9") (pin "4") (pinfunction "4_4") (pintype "passive"))
      (node (ref "P3") (pin "2") (pinfunction "2_2") (pintype "passive"))
    )
    (net (code "34") (name "/Ad22") (class "Default")
      (node (ref "K10") (pin "4") (pinfunction "4_4") (pintype "passive"))
      (node (ref "P3") (pin "10") (pinfunction "10_10") (pintype "passive"))
    )
    (net (code "35") (name "/Ad23") (class "Default")
      (node (ref "K11") (pin "4") (pinfunction "4_4") (pintype "passive"))
      (node (ref "P3") (pin "18") (pinfunction "18_18") (pintype "passive"))
    )
    (net (code "36") (name "/Ad24") (class "Default")
      (node (ref "K12") (pin "4") (pinfunction "4_4") (pintype "passive"))
      (node (ref "P3") (pin "26") (pinfunction "26_26") (pintype "passive"))
    )
    (net (code "37") (name "/Ad25") (class "Default")
      (node (ref "K13") (pin "4") (pinfunction "4_4") (pintype "passive"))
      (node (ref "P4") (pin "1") (pinfunction "1_1") (pintype "passive"))
    )
    (net (code "38") (name "/Ad26") (class "Default")
      (node (ref "K14") (pin "4") (pinfunction "4_4") (pintype "passive"))
      (node (ref "P4") (pin "5") (pinfunction "5_5") (pintype "passive"))
    )
    (net (code "39") (name "/Ad27") (class "Default")
      (node (ref "K15") (pin "4") (pinfunction "4_4") (pintype "passive"))
      (node (ref "P4") (pin "9") (pinfunction "9_9") (pintype "passive"))
    )
    (net (code "40") (name "/Ad28") (class "Default")
      (node (ref "K16") (pin "4") (pinfunction "4_4") (pintype "passive"))
      (node (ref "P4") (pin "13") (pinfunction "13_13") (pintype "passive"))
    )
    (net (code "41") (name "/Ad31") (class "Default")
      (node (ref "K17") (pin "4") (pinfunction "4_4") (pintype "passive"))
      (node (ref "P5") (pin "2") (pinfunction "2_2") (pintype "passive"))
    )
    (net (code "42") (name "/Ad32") (class "Default")
      (node (ref "K18") (pin "4") (pinfunction "4_4") (pintype "passive"))
      (node (ref "P5") (pin "10") (pinfunction "10_10") (pintype "passive"))
    )
    (net (code "43") (name "/Ad33") (class "Default")
      (node (ref "K19") (pin "4") (pinfunction "4_4") (pintype "passive"))
      (node (ref "P5") (pin "18") (pinfunction "18_18") (pintype "passive"))
    )
    (net (code "44") (name "/Ad34") (class "Default")
      (node (ref "K20") (pin "4") (pinfunction "4_4") (pintype "passive"))
      (node (ref "P5") (pin "26") (pinfunction "26_26") (pintype "passive"))
    )
    (net (code "45") (name "/Ad35") (class "Default")
      (node (ref "K21") (pin "4") (pinfunction "4_4") (pintype "passive"))
      (node (ref "P6") (pin "1") (pinfunction "1_1") (pintype "passive"))
    )
    (net (code "46") (name "/Ad36") (class "Default")
      (node (ref "K22") (pin "4") (pinfunction "4_4") (pintype "passive"))
      (node (ref "P6") (pin "5") (pinfunction "5_5") (pintype "passive"))
    )
    (net (code "47") (name "/Ad37") (class "Default")
      (node (ref "K23") (pin "4") (pinfunction "4_4") (pintype "passive"))
      (node (ref "P6") (pin "9") (pinfunction "9_9") (pintype "passive"))
    )
    (net (code "48") (name "/Ad38") (class "Default")
      (node (ref "K24") (pin "4") (pinfunction "4_4") (pintype "passive"))
      (node (ref "P6") (pin "13") (pinfunction "13_13") (pintype "passive"))
    )
    (net (code "49") (name "/Ad41") (class "Default")
      (node (ref "K30") (pin "4") (pinfunction "4_4") (pintype "passive"))
      (node (ref "P7") (pin "2") (pinfunction "2_2") (pintype "passive"))
    )
    (net (code "50") (name "/Ad42") (class "Default")
      (node (ref "K29") (pin "4") (pinfunction "4_4") (pintype "passive"))
      (node (ref "P7") (pin "10") (pinfunction "10_10") (pintype "passive"))
    )
    (net (code "51") (name "/Ad43") (class "Default")
      (node (ref "K28") (pin "4") (pinfunction "4_4") (pintype "passive"))
      (node (ref "P7") (pin "18") (pinfunction "18_18") (pintype "passive"))
    )
    (net (code "52") (name "/Ad44") (class "Default")
      (node (ref "K27") (pin "4") (pinfunction "4_4") (pintype "passive"))
      (node (ref "P7") (pin "26") (pinfunction "26_26") (pintype "passive"))
    )
    (net (code "53") (name "/Ad45") (class "Default")
      (node (ref "K26") (pin "4") (pinfunction "4_4") (pintype "passive"))
      (node (ref "P7") (pin "34") (pinfunction "34_34") (pintype "passive"))
    )
    (net (code "54") (name "/Ad46") (class "Default")
      (node (ref "K25") (pin "4") (pinfunction "4_4") (pintype "passive"))
      (node (ref "P7") (pin "42") (pinfunction "42_42") (pintype "passive"))
    )
    (net (code "55") (name "/As11") (class "Default")
      (node (ref "P1") (pin "1") (pinfunction "1_1") (pintype "passive"))
      (node (ref "R1") (pin "2") (pintype "passive"))
    )
    (net (code "56") (name "/As12") (class "Default")
      (node (ref "P1") (pin "9") (pinfunction "9_9") (pintype "passive"))
      (node (ref "R3") (pin "2") (pintype "passive"))
    )
    (net (code "57") (name "/As13") (class "Default")
      (node (ref "P1") (pin "17") (pinfunction "17_17") (pintype "passive"))
      (node (ref "R5") (pin "2") (pintype "passive"))
    )
    (net (code "58") (name "/As14") (class "Default")
      (node (ref "P1") (pin "25") (pinfunction "25_25") (pintype "passive"))
      (node (ref "R7") (pin "2") (pintype "passive"))
    )
    (net (code "59") (name "/As18") (class "Default")
      (node (ref "P2") (pin "17") (pinfunction "17_17") (pintype "passive"))
      (node (ref "R9") (pin "2") (pintype "passive"))
    )
    (net (code "60") (name "/As21") (class "Default")
      (node (ref "P3") (pin "1") (pinfunction "1_1") (pintype "passive"))
      (node (ref "R27") (pin "2") (pintype "passive"))
    )
    (net (code "61") (name "/As22") (class "Default")
      (node (ref "P3") (pin "9") (pinfunction "9_9") (pintype "passive"))
      (node (ref "R29") (pin "2") (pintype "passive"))
    )
    (net (code "62") (name "/As23") (class "Default")
      (node (ref "P3") (pin "17") (pinfunction "17_17") (pintype "passive"))
      (node (ref "R31") (pin "2") (pintype "passive"))
    )
    (net (code "63") (name "/As24") (class "Default")
      (node (ref "P3") (pin "25") (pinfunction "25_25") (pintype "passive"))
      (node (ref "R33") (pin "2") (pintype "passive"))
    )
    (net (code "64") (name "/As28") (class "Default")
      (node (ref "P4") (pin "17") (pinfunction "17_17") (pintype "passive"))
      (node (ref "R35") (pin "2") (pintype "passive"))
    )
    (net (code "65") (name "/As31") (class "Default")
      (node (ref "P5") (pin "1") (pinfunction "1_1") (pintype "passive"))
      (node (ref "R55") (pin "2") (pintype "passive"))
    )
    (net (code "66") (name "/As32") (class "Default")
      (node (ref "P5") (pin "9") (pinfunction "9_9") (pintype "passive"))
      (node (ref "R57") (pin "2") (pintype "passive"))
    )
    (net (code "67") (name "/As33") (class "Default")
      (node (ref "P5") (pin "17") (pinfunction "17_17") (pintype "passive"))
      (node (ref "R59") (pin "2") (pintype "passive"))
    )
    (net (code "68") (name "/As34") (class "Default")
      (node (ref "P5") (pin "25") (pinfunction "25_25") (pintype "passive"))
      (node (ref "R61") (pin "2") (pintype "passive"))
    )
    (net (code "69") (name "/As38") (class "Default")
      (node (ref "P6") (pin "17") (pinfunction "17_17") (pintype "passive"))
      (node (ref "R63") (pin "2") (pintype "passive"))
    )
    (net (code "70") (name "/As41") (class "Default")
      (node (ref "K30") (pin "3") (pinfunction "3_3") (pintype "passive"))
      (node (ref "P7") (pin "1") (pinfunction "1_1") (pintype "passive"))
    )
    (net (code "71") (name "/As42") (class "Default")
      (node (ref "K29") (pin "3") (pinfunction "3_3") (pintype "passive"))
      (node (ref "P7") (pin "9") (pinfunction "9_9") (pintype "passive"))
    )
    (net (code "72") (name "/As43") (class "Default")
      (node (ref "K28") (pin "3") (pinfunction "3_3") (pintype "passive"))
      (node (ref "P7") (pin "17") (pinfunction "17_17") (pintype "passive"))
    )
    (net (code "73") (name "/As44") (class "Default")
      (node (ref "K27") (pin "3") (pinfunction "3_3") (pintype "passive"))
      (node (ref "P7") (pin "25") (pinfunction "25_25") (pintype "passive"))
    )
    (net (code "74") (name "/As45") (class "Default")
      (node (ref "K26") (pin "3") (pinfunction "3_3") (pintype "passive"))
      (node (ref "P7") (pin "33") (pinfunction "33_33") (pintype "passive"))
    )
    (net (code "75") (name "/As46") (class "Default")
      (node (ref "K25") (pin "3") (pinfunction "3_3") (pintype "passive"))
      (node (ref "P7") (pin "41") (pinfunction "41_41") (pintype "passive"))
    )
    (net (code "76") (name "/B1") (class "Default")
      (node (ref "K1") (pin "6") (pinfunction "6_6") (pintype "passive"))
      (node (ref "R18") (pin "1") (pintype "passive"))
      (node (ref "R2") (pin "1") (pintype "passive"))
      (node (ref "R26") (pin "2") (pintype "passive"))
    )
    (net (code "77") (name "/B2") (class "Default")
      (node (ref "K16") (pin "6") (pinfunction "6_6") (pintype "passive"))
      (node (ref "R26") (pin "1") (pintype "passive"))
      (node (ref "R36") (pin "1") (pintype "passive"))
      (node (ref "R51") (pin "2") (pintype "passive"))
    )
    (net (code "78") (name "/B22") (class "Default")
      (node (ref "K9") (pin "6") (pinfunction "6_6") (pintype "passive"))
      (node (ref "R28") (pin "1") (pintype "passive"))
      (node (ref "R45") (pin "1") (pintype "passive"))
      (node (ref "R53") (pin "2") (pintype "passive"))
    )
    (net (code "79") (name "/B23") (class "Default")
      (node (ref "K24") (pin "6") (pinfunction "6_6") (pintype "passive"))
      (node (ref "R53") (pin "1") (pintype "passive"))
      (node (ref "R64") (pin "1") (pintype "passive"))
      (node (ref "R78") (pin "2") (pintype "passive"))
    )
    (net (code "80") (name "/Bc11") (class "Default")
      (node (ref "K1") (pin "7") (pinfunction "7_7") (pintype "passive"))
      (node (ref "P1") (pin "7") (pinfunction "7_7") (pintype "passive"))
    )
    (net (code "81") (name "/Bc12") (class "Default")
      (node (ref "K2") (pin "7") (pinfunction "7_7") (pintype "passive"))
      (node (ref "P1") (pin "15") (pinfunction "15_15") (pintype "passive"))
    )
    (net (code "82") (name "/Bc13") (class "Default")
      (node (ref "K3") (pin "7") (pinfunction "7_7") (pintype "passive"))
      (node (ref "P1") (pin "23") (pinfunction "23_23") (pintype "passive"))
    )
    (net (code "83") (name "/Bc14") (class "Default")
      (node (ref "K4") (pin "7") (pinfunction "7_7") (pintype "passive"))
      (node (ref "P1") (pin "31") (pinfunction "31_31") (pintype "passive"))
    )
    (net (code "84") (name "/Bc21") (class "Default")
      (node (ref "K9") (pin "7") (pinfunction "7_7") (pintype "passive"))
      (node (ref "P3") (pin "7") (pinfunction "7_7") (pintype "passive"))
    )
    (net (code "85") (name "/Bc22") (class "Default")
      (node (ref "K10") (pin "7") (pinfunction "7_7") (pintype "passive"))
      (node (ref "P3") (pin "15") (pinfunction "15_15") (pintype "passive"))
    )
    (net (code "86") (name "/Bc23") (class "Default")
      (node (ref "K11") (pin "7") (pinfunction "7_7") (pintype "passive"))
      (node (ref "P3") (pin "23") (pinfunction "23_23") (pintype "passive"))
    )
    (net (code "87") (name "/Bc24") (class "Default")
      (node (ref "K12") (pin "7") (pinfunction "7_7") (pintype "passive"))
      (node (ref "P3") (pin "31") (pinfunction "31_31") (pintype "passive"))
    )
    (net (code "88") (name "/Bc31") (class "Default")
      (node (ref "K17") (pin "7") (pinfunction "7_7") (pintype "passive"))
      (node (ref "P5") (pin "7") (pinfunction "7_7") (pintype "passive"))
    )
    (net (code "89") (name "/Bc32") (class "Default")
      (node (ref "K18") (pin "7") (pinfunction "7_7") (pintype "passive"))
      (node (ref "P5") (pin "15") (pinfunction "15_15") (pintype "passive"))
    )
    (net (code "90") (name "/Bc33") (class "Default")
      (node (ref "K19") (pin "7") (pinfunction "7_7") (pintype "passive"))
      (node (ref "P5") (pin "23") (pinfunction "23_23") (pintype "passive"))
    )
    (net (code "91") (name "/Bc34") (class "Default")
      (node (ref "K20") (pin "7") (pinfunction "7_7") (pintype "passive"))
      (node (ref "P5") (pin "31") (pinfunction "31_31") (pintype "passive"))
    )
    (net (code "92") (name "/Bc41") (class "Default")
      (node (ref "K30") (pin "7") (pinfunction "7_7") (pintype "passive"))
      (node (ref "P7") (pin "7") (pinfunction "7_7") (pintype "passive"))
    )
    (net (code "93") (name "/Bc42") (class "Default")
      (node (ref "K29") (pin "7") (pinfunction "7_7") (pintype "passive"))
      (node (ref "P7") (pin "15") (pinfunction "15_15") (pintype "passive"))
    )
    (net (code "94") (name "/Bc43") (class "Default")
      (node (ref "K28") (pin "7") (pinfunction "7_7") (pintype "passive"))
      (node (ref "P7") (pin "23") (pinfunction "23_23") (pintype "passive"))
    )
    (net (code "95") (name "/Bc44") (class "Default")
      (node (ref "K27") (pin "7") (pinfunction "7_7") (pintype "passive"))
      (node (ref "P7") (pin "31") (pinfunction "31_31") (pintype "passive"))
    )
    (net (code "96") (name "/Bc45") (class "Default")
      (node (ref "K26") (pin "7") (pinfunction "7_7") (pintype "passive"))
      (node (ref "P7") (pin "39") (pinfunction "39_39") (pintype "passive"))
    )
    (net (code "97") (name "/Bc46") (class "Default")
      (node (ref "K25") (pin "7") (pinfunction "7_7") (pintype "passive"))
      (node (ref "P7") (pin "47") (pinfunction "47_47") (pintype "passive"))
    )
    (net (code "98") (name "/Bd11") (class "Default")
      (node (ref "K1") (pin "5") (pinfunction "5_5") (pintype "passive"))
      (node (ref "P1") (pin "6") (pinfunction "6_6") (pintype "passive"))
    )
    (net (code "99") (name "/Bd12") (class "Default")
      (node (ref "K2") (pin "5") (pinfunction "5_5") (pintype "passive"))
      (node (ref "P1") (pin "14") (pinfunction "14_14") (pintype "passive"))
    )
    (net (code "100") (name "/Bd13") (class "Default")
      (node (ref "K3") (pin "5") (pinfunction "5_5") (pintype "passive"))
      (node (ref "P1") (pin "22") (pinfunction "22_22") (pintype "passive"))
    )
    (net (code "101") (name "/Bd14") (class "Default")
      (node (ref "K4") (pin "5") (pinfunction "5_5") (pintype "passive"))
      (node (ref "P1") (pin "30") (pinfunction "30_30") (pintype "passive"))
    )
    (net (code "102") (name "/Bd15") (class "Default")
      (node (ref "K5") (pin "5") (pinfunction "5_5") (pintype "passive"))
      (node (ref "P2") (pin "3") (pinfunction "3_3") (pintype "passive"))
    )
    (net (code "103") (name "/Bd16") (class "Default")
      (node (ref "K6") (pin "5") (pinfunction "5_5") (pintype "passive"))
      (node (ref "P2") (pin "7") (pinfunction "7_7") (pintype "passive"))
    )
    (net (code "104") (name "/Bd17") (class "Default")
      (node (ref "K7") (pin "5") (pinfunction "5_5") (pintype "passive"))
      (node (ref "P2") (pin "11") (pinfunction "11_11") (pintype "passive"))
    )
    (net (code "105") (name "/Bd18") (class "Default")
      (node (ref "K8") (pin "5") (pinfunction "5_5") (pintype "passive"))
      (node (ref "P2") (pin "15") (pinfunction "15_15") (pintype "passive"))
    )
    (net (code "106") (name "/Bd21") (class "Default")
      (node (ref "K9") (pin "5") (pinfunction "5_5") (pintype "passive"))
      (node (ref "P3") (pin "6") (pinfunction "6_6") (pintype "passive"))
    )
    (net (code "107") (name "/Bd22") (class "Default")
      (node (ref "K10") (pin "5") (pinfunction "5_5") (pintype "passive"))
      (node (ref "P3") (pin "14") (pinfunction "14_14") (pintype "passive"))
    )
    (net (code "108") (name "/Bd23") (class "Default")
      (node (ref "K11") (pin "5") (pinfunction "5_5") (pintype "passive"))
      (node (ref "P3") (pin "22") (pinfunction "22_22") (pintype "passive"))
    )
    (net (code "109") (name "/Bd24") (class "Default")
      (node (ref "K12") (pin "5") (pinfunction "5_5") (pintype "passive"))
      (node (ref "P3") (pin "30") (pinfunction "30_30") (pintype "passive"))
    )
    (net (code "110") (name "/Bd25") (class "Default")
      (node (ref "K13") (pin "5") (pinfunction "5_5") (pintype "passive"))
      (node (ref "P4") (pin "3") (pinfunction "3_3") (pintype "passive"))
    )
    (net (code "111") (name "/Bd26") (class "Default")
      (node (ref "K14") (pin "5") (pinfunction "5_5") (pintype "passive"))
      (node (ref "P4") (pin "7") (pinfunction "7_7") (pintype "passive"))
    )
    (net (code "112") (name "/Bd27") (class "Default")
      (node (ref "K15") (pin "5") (pinfunction "5_5") (pintype "passive"))
      (node (ref "P4") (pin "11") (pinfunction "11_11") (pintype "passive"))
    )
    (net (code "113") (name "/Bd28") (class "Default")
      (node (ref "K16") (pin "5") (pinfunction "5_5") (pintype "passive"))
      (node (ref "P4") (pin "15") (pinfunction "15_15") (pintype "passive"))
    )
    (net (code "114") (name "/Bd31") (class "Default")
      (node (ref "K17") (pin "5") (pinfunction "5_5") (pintype "passive"))
      (node (ref "P5") (pin "6") (pinfunction "6_6") (pintype "passive"))
    )
    (net (code "115") (name "/Bd32") (class "Default")
      (node (ref "K18") (pin "5") (pinfunction "5_5") (pintype "passive"))
      (node (ref "P5") (pin "14") (pinfunction "14_14") (pintype "passive"))
    )
    (net (code "116") (name "/Bd33") (class "Default")
      (node (ref "K19") (pin "5") (pinfunction "5_5") (pintype "passive"))
      (node (ref "P5") (pin "22") (pinfunction "22_22") (pintype "passive"))
    )
    (net (code "117") (name "/Bd34") (class "Default")
      (node (ref "K20") (pin "5") (pinfunction "5_5") (pintype "passive"))
      (node (ref "P5") (pin "30") (pinfunction "30_30") (pintype "passive"))
    )
    (net (code "118") (name "/Bd35") (class "Default")
      (node (ref "K21") (pin "5") (pinfunction "5_5") (pintype "passive"))
      (node (ref "P6") (pin "3") (pinfunction "3_3") (pintype "passive"))
    )
    (net (code "119") (name "/Bd36") (class "Default")
      (node (ref "K22") (pin "5") (pinfunction "5_5") (pintype "passive"))
      (node (ref "P6") (pin "7") (pinfunction "7_7") (pintype "passive"))
    )
    (net (code "120") (name "/Bd37") (class "Default")
      (node (ref "K23") (pin "5") (pinfunction "5_5") (pintype "passive"))
      (node (ref "P6") (pin "11") (pinfunction "11_11") (pintype "passive"))
    )
    (net (code "121") (name "/Bd38") (class "Default")
      (node (ref "K24") (pin "5") (pinfunction "5_5") (pintype "passive"))
      (node (ref "P6") (pin "15") (pinfunction "15_15") (pintype "passive"))
    )
    (net (code "122") (name "/Bd41") (class "Default")
      (node (ref "K30") (pin "5") (pinfunction "5_5") (pintype "passive"))
      (node (ref "P7") (pin "6") (pinfunction "6_6") (pintype "passive"))
    )
    (net (code "123") (name "/Bd42") (class "Default")
      (node (ref "K29") (pin "5") (pinfunction "5_5") (pintype "passive"))
      (node (ref "P7") (pin "14") (pinfunction "14_14") (pintype "passive"))
    )
    (net (code "124") (name "/Bd43") (class "Default")
      (node (ref "K28") (pin "5") (pinfunction "5_5") (pintype "passive"))
      (node (ref "P7") (pin "22") (pinfunction "22_22") (pintype "passive"))
    )
    (net (code "125") (name "/Bd44") (class "Default")
      (node (ref "K27") (pin "5") (pinfunction "5_5") (pintype "passive"))
      (node (ref "P7") (pin "30") (pinfunction "30_30") (pintype "passive"))
    )
    (net (code "126") (name "/Bd45") (class "Default")
      (node (ref "K26") (pin "5") (pinfunction "5_5") (pintype "passive"))
      (node (ref "P7") (pin "38") (pinfunction "38_38") (pintype "passive"))
    )
    (net (code "127") (name "/Bd46") (class "Default")
      (node (ref "K25") (pin "5") (pinfunction "5_5") (pintype "passive"))
      (node (ref "P7") (pin "46") (pinfunction "46_46") (pintype "passive"))
    )
    (net (code "128") (name "/Bs11") (class "Default")
      (node (ref "P1") (pin "5") (pinfunction "5_5") (pintype "passive"))
      (node (ref "R2") (pin "2") (pintype "passive"))
    )
    (net (code "129") (name "/Bs12") (class "Default")
      (node (ref "P1") (pin "13") (pinfunction "13_13") (pintype "passive"))
      (node (ref "R4") (pin "2") (pintype "passive"))
    )
    (net (code "130") (name "/Bs13") (class "Default")
      (node (ref "P1") (pin "21") (pinfunction "21_21") (pintype "passive"))
      (node (ref "R6") (pin "2") (pintype "passive"))
    )
    (net (code "131") (name "/Bs14") (class "Default")
      (node (ref "P1") (pin "29") (pinfunction "29_29") (pintype "passive"))
      (node (ref "R8") (pin "2") (pintype "passive"))
    )
    (net (code "132") (name "/Bs18") (class "Default")
      (node (ref "P2") (pin "19") (pinfunction "19_19") (pintype "passive"))
      (node (ref "R10") (pin "2") (pintype "passive"))
    )
    (net (code "133") (name "/Bs21") (class "Default")
      (node (ref "P3") (pin "5") (pinfunction "5_5") (pintype "passive"))
      (node (ref "R28") (pin "2") (pintype "passive"))
    )
    (net (code "134") (name "/Bs22") (class "Default")
      (node (ref "P3") (pin "13") (pinfunction "13_13") (pintype "passive"))
      (node (ref "R30") (pin "2") (pintype "passive"))
    )
    (net (code "135") (name "/Bs23") (class "Default")
      (node (ref "P3") (pin "21") (pinfunction "21_21") (pintype "passive"))
      (node (ref "R32") (pin "2") (pintype "passive"))
    )
    (net (code "136") (name "/Bs24") (class "Default")
      (node (ref "P3") (pin "29") (pinfunction "29_29") (pintype "passive"))
      (node (ref "R34") (pin "2") (pintype "passive"))
    )
    (net (code "137") (name "/Bs28") (class "Default")
      (node (ref "P4") (pin "19") (pinfunction "19_19") (pintype "passive"))
      (node (ref "R36") (pin "2") (pintype "passive"))
    )
    (net (code "138") (name "/Bs31") (class "Default")
      (node (ref "P5") (pin "5") (pinfunction "5_5") (pintype "passive"))
      (node (ref "R56") (pin "2") (pintype "passive"))
    )
    (net (code "139") (name "/Bs32") (class "Default")
      (node (ref "P5") (pin "13") (pinfunction "13_13") (pintype "passive"))
      (node (ref "R58") (pin "2") (pintype "passive"))
    )
    (net (code "140") (name "/Bs33") (class "Default")
      (node (ref "P5") (pin "21") (pinfunction "21_21") (pintype "passive"))
      (node (ref "R60") (pin "2") (pintype "passive"))
    )
    (net (code "141") (name "/Bs34") (class "Default")
      (node (ref "P5") (pin "29") (pinfunction "29_29") (pintype "passive"))
      (node (ref "R62") (pin "2") (pintype "passive"))
    )
    (net (code "142") (name "/Bs38") (class "Default")
      (node (ref "P6") (pin "19") (pinfunction "19_19") (pintype "passive"))
      (node (ref "R64") (pin "2") (pintype "passive"))
    )
    (net (code "143") (name "/Bs41") (class "Default")
      (node (ref "K30") (pin "6") (pinfunction "6_6") (pintype "passive"))
      (node (ref "P7") (pin "5") (pinfunction "5_5") (pintype "passive"))
    )
    (net (code "144") (name "/Bs42") (class "Default")
      (node (ref "K29") (pin "6") (pinfunction "6_6") (pintype "passive"))
      (node (ref "P7") (pin "13") (pinfunction "13_13") (pintype "passive"))
    )
    (net (code "145") (name "/Bs43") (class "Default")
      (node (ref "K28") (pin "6") (pinfunction "6_6") (pintype "passive"))
      (node (ref "P7") (pin "21") (pinfunction "21_21") (pintype "passive"))
    )
    (net (code "146") (name "/Bs44") (class "Default")
      (node (ref "K27") (pin "6") (pinfunction "6_6") (pintype "passive"))
      (node (ref "P7") (pin "29") (pinfunction "29_29") (pintype "passive"))
    )
    (net (code "147") (name "/Bs45") (class "Default")
      (node (ref "K26") (pin "6") (pinfunction "6_6") (pintype "passive"))
      (node (ref "P7") (pin "37") (pinfunction "37_37") (pintype "passive"))
    )
    (net (code "148") (name "/Bs46") (class "Default")
      (node (ref "K25") (pin "6") (pinfunction "6_6") (pintype "passive"))
      (node (ref "P7") (pin "45") (pinfunction "45_45") (pintype "passive"))
    )
    (net (code "149") (name "/R11") (class "Default")
      (node (ref "K1") (pin "8") (pinfunction "8_8") (pintype "passive"))
      (node (ref "ULN2") (pin "10") (pinfunction "C8_10") (pintype "passive"))
    )
    (net (code "150") (name "/R12") (class "Default")
      (node (ref "K2") (pin "8") (pinfunction "8_8") (pintype "passive"))
      (node (ref "ULN2") (pin "11") (pinfunction "C7_11") (pintype "passive"))
    )
    (net (code "151") (name "/R13") (class "Default")
      (node (ref "K3") (pin "8") (pinfunction "8_8") (pintype "passive"))
      (node (ref "ULN2") (pin "12") (pinfunction "C6_12") (pintype "passive"))
    )
    (net (code "152") (name "/R14") (class "Default")
      (node (ref "K4") (pin "8") (pinfunction "8_8") (pintype "passive"))
      (node (ref "ULN2") (pin "13") (pinfunction "C5_13") (pintype "passive"))
    )
    (net (code "153") (name "/R15") (class "Default")
      (node (ref "K5") (pin "8") (pinfunction "8_8") (pintype "passive"))
      (node (ref "ULN2") (pin "14") (pinfunction "C4_14") (pintype "passive"))
    )
    (net (code "154") (name "/R16") (class "Default")
      (node (ref "K6") (pin "8") (pinfunction "8_8") (pintype "passive"))
      (node (ref "ULN2") (pin "15") (pinfunction "C3_15") (pintype "passive"))
    )
    (net (code "155") (name "/R17") (class "Default")
      (node (ref "K7") (pin "8") (pinfunction "8_8") (pintype "passive"))
      (node (ref "ULN2") (pin "16") (pinfunction "C2_16") (pintype "passive"))
    )
    (net (code "156") (name "/R18") (class "Default")
      (node (ref "K8") (pin "8") (pinfunction "8_8") (pintype "passive"))
      (node (ref "ULN2") (pin "17") (pinfunction "C1_17") (pintype "passive"))
    )
    (net (code "157") (name "/R21") (class "Default")
      (node (ref "K9") (pin "8") (pinfunction "8_8") (pintype "passive"))
      (node (ref "ULN1") (pin "10") (pinfunction "C8_10") (pintype "passive"))
    )
    (net (code "158") (name "/R22") (class "Default")
      (node (ref "K10") (pin "8") (pinfunction "8_8") (pintype "passive"))
      (node (ref "ULN1") (pin "11") (pinfunction "C7_11") (pintype "passive"))
    )
    (net (code "159") (name "/R23") (class "Default")
      (node (ref "K11") (pin "8") (pinfunction "8_8") (pintype "passive"))
      (node (ref "ULN1") (pin "12") (pinfunction "C6_12") (pintype "passive"))
    )
    (net (code "160") (name "/R24") (class "Default")
      (node (ref "K12") (pin "8") (pinfunction "8_8") (pintype "passive"))
      (node (ref "ULN1") (pin "13") (pinfunction "C5_13") (pintype "passive"))
    )
    (net (code "161") (name "/R25") (class "Default")
      (node (ref "K13") (pin "8") (pinfunction "8_8") (pintype "passive"))
      (node (ref "ULN1") (pin "14") (pinfunction "C4_14") (pintype "passive"))
    )
    (net (code "162") (name "/R26") (class "Default")
      (node (ref "K14") (pin "8") (pinfunction "8_8") (pintype "passive"))
      (node (ref "ULN1") (pin "15") (pinfunction "C3_15") (pintype "passive"))
    )
    (net (code "163") (name "/R27") (class "Default")
      (node (ref "K15") (pin "8") (pinfunction "8_8") (pintype "passive"))
      (node (ref "ULN1") (pin "16") (pinfunction "C2_16") (pintype "passive"))
    )
    (net (code "164") (name "/R28") (class "Default")
      (node (ref "K16") (pin "8") (pinfunction "8_8") (pintype "passive"))
      (node (ref "ULN1") (pin "17") (pinfunction "C1_17") (pintype "passive"))
    )
    (net (code "165") (name "/R31") (class "Default")
      (node (ref "K17") (pin "8") (pinfunction "8_8") (pintype "passive"))
      (node (ref "ULN3") (pin "10") (pinfunction "C8_10") (pintype "passive"))
    )
    (net (code "166") (name "/R32") (class "Default")
      (node (ref "K18") (pin "8") (pinfunction "8_8") (pintype "passive"))
      (node (ref "ULN3") (pin "11") (pinfunction "C7_11") (pintype "passive"))
    )
    (net (code "167") (name "/R33") (class "Default")
      (node (ref "K19") (pin "8") (pinfunction "8_8") (pintype "passive"))
      (node (ref "ULN3") (pin "12") (pinfunction "C6_12") (pintype "passive"))
    )
    (net (code "168") (name "/R34") (class "Default")
      (node (ref "K20") (pin "8") (pinfunction "8_8") (pintype "passive"))
      (node (ref "ULN3") (pin "13") (pinfunction "C5_13") (pintype "passive"))
    )
    (net (code "169") (name "/R35") (class "Default")
      (node (ref "K21") (pin "8") (pinfunction "8_8") (pintype "passive"))
      (node (ref "ULN3") (pin "14") (pinfunction "C4_14") (pintype "passive"))
    )
    (net (code "170") (name "/R36") (class "Default")
      (node (ref "K22") (pin "8") (pinfunction "8_8") (pintype "passive"))
      (node (ref "ULN3") (pin "15") (pinfunction "C3_15") (pintype "passive"))
    )
    (net (code "171") (name "/R37") (class "Default")
      (node (ref "K23") (pin "8") (pinfunction "8_8") (pintype "passive"))
      (node (ref "ULN3") (pin "16") (pinfunction "C2_16") (pintype "passive"))
    )
    (net (code "172") (name "/R38") (class "Default")
      (node (ref "K24") (pin "8") (pinfunction "8_8") (pintype "passive"))
      (node (ref "ULN3") (pin "17") (pinfunction "C1_17") (pintype "passive"))
    )
    (net (code "173") (name "/R41") (class "Default")
      (node (ref "K30") (pin "8") (pinfunction "8_8") (pintype "passive"))
      (node (ref "ULN4") (pin "12") (pinfunction "C6_12") (pintype "passive"))
    )
    (net (code "174") (name "/R42") (class "Default")
      (node (ref "K29") (pin "8") (pinfunction "8_8") (pintype "passive"))
      (node (ref "ULN4") (pin "13") (pinfunction "C5_13") (pintype "passive"))
    )
    (net (code "175") (name "/R43") (class "Default")
      (node (ref "K28") (pin "8") (pinfunction "8_8") (pintype "passive"))
      (node (ref "ULN4") (pin "14") (pinfunction "C4_14") (pintype "passive"))
    )
    (net (code "176") (name "/R44") (class "Default")
      (node (ref "K27") (pin "8") (pinfunction "8_8") (pintype "passive"))
      (node (ref "ULN4") (pin "15") (pinfunction "C3_15") (pintype "passive"))
    )
    (net (code "177") (name "/R45") (class "Default")
      (node (ref "K26") (pin "8") (pinfunction "8_8") (pintype "passive"))
      (node (ref "ULN4") (pin "16") (pinfunction "C2_16") (pintype "passive"))
    )
    (net (code "178") (name "/R46") (class "Default")
      (node (ref "K25") (pin "8") (pinfunction "8_8") (pintype "passive"))
      (node (ref "ULN4") (pin "17") (pinfunction "C1_17") (pintype "passive"))
    )
    (net (code "179") (name "/SCL_DRV") (class "Default")
      (node (ref "MCP1") (pin "8") (pinfunction "SCL_8") (pintype "passive"))
      (node (ref "MCP2") (pin "8") (pinfunction "SCL_8") (pintype "passive"))
    )
    (net (code "180") (name "/SDA_DRV") (class "Default")
      (node (ref "MCP1") (pin "9") (pinfunction "SDA_9") (pintype "passive"))
      (node (ref "MCP2") (pin "9") (pinfunction "SDA_9") (pintype "passive"))
    )
    (net (code "181") (name "AGND1") (class "Default")
      (node (ref "P1") (pin "12") (pinfunction "12_12") (pintype "passive"))
      (node (ref "P1") (pin "16") (pinfunction "16_16") (pintype "passive"))
      (node (ref "P1") (pin "20") (pinfunction "20_20") (pintype "passive"))
      (node (ref "P1") (pin "24") (pinfunction "24_24") (pintype "passive"))
      (node (ref "P1") (pin "28") (pinfunction "28_28") (pintype "passive"))
      (node (ref "P1") (pin "32") (pinfunction "32_32") (pintype "passive"))
      (node (ref "P1") (pin "4") (pinfunction "4_4") (pintype "passive"))
      (node (ref "P1") (pin "8") (pinfunction "8_8") (pintype "passive"))
      (node (ref "P2") (pin "10") (pinfunction "10_10") (pintype "passive"))
      (node (ref "P2") (pin "12") (pinfunction "12_12") (pintype "passive"))
      (node (ref "P2") (pin "14") (pinfunction "14_14") (pintype "passive"))
      (node (ref "P2") (pin "16") (pinfunction "16_16") (pintype "passive"))
      (node (ref "P2") (pin "18") (pinfunction "18_18") (pintype "passive"))
      (node (ref "P2") (pin "2") (pinfunction "2_2") (pintype "passive"))
      (node (ref "P2") (pin "20") (pinfunction "20_20") (pintype "passive"))
      (node (ref "P2") (pin "4") (pinfunction "4_4") (pintype "passive"))
      (node (ref "P2") (pin "6") (pinfunction "6_6") (pintype "passive"))
      (node (ref "P2") (pin "8") (pinfunction "8_8") (pintype "passive"))
    )
    (net (code "182") (name "AGND2") (class "Default")
      (node (ref "P3") (pin "12") (pinfunction "12_12") (pintype "passive"))
      (node (ref "P3") (pin "16") (pinfunction "16_16") (pintype "passive"))
      (node (ref "P3") (pin "20") (pinfunction "20_20") (pintype "passive"))
      (node (ref "P3") (pin "24") (pinfunction "24_24") (pintype "passive"))
      (node (ref "P3") (pin "28") (pinfunction "28_28") (pintype "passive"))
      (node (ref "P3") (pin "32") (pinfunction "32_32") (pintype "passive"))
      (node (ref "P3") (pin "4") (pinfunction "4_4") (pintype "passive"))
      (node (ref "P3") (pin "8") (pinfunction "8_8") (pintype "passive"))
      (node (ref "P4") (pin "10") (pinfunction "10_10") (pintype "passive"))
      (node (ref "P4") (pin "12") (pinfunction "12_12") (pintype "passive"))
      (node (ref "P4") (pin "14") (pinfunction "14_14") (pintype "passive"))
      (node (ref "P4") (pin "16") (pinfunction "16_16") (pintype "passive"))
      (node (ref "P4") (pin "18") (pinfunction "18_18") (pintype "passive"))
      (node (ref "P4") (pin "2") (pinfunction "2_2") (pintype "passive"))
      (node (ref "P4") (pin "20") (pinfunction "20_20") (pintype "passive"))
      (node (ref "P4") (pin "4") (pinfunction "4_4") (pintype "passive"))
      (node (ref "P4") (pin "6") (pinfunction "6_6") (pintype "passive"))
      (node (ref "P4") (pin "8") (pinfunction "8_8") (pintype "passive"))
    )
    (net (code "183") (name "AGND3") (class "Default")
      (node (ref "P5") (pin "12") (pinfunction "12_12") (pintype "passive"))
      (node (ref "P5") (pin "16") (pinfunction "16_16") (pintype "passive"))
      (node (ref "P5") (pin "20") (pinfunction "20_20") (pintype "passive"))
      (node (ref "P5") (pin "24") (pinfunction "24_24") (pintype "passive"))
      (node (ref "P5") (pin "28") (pinfunction "28_28") (pintype "passive"))
      (node (ref "P5") (pin "32") (pinfunction "32_32") (pintype "passive"))
      (node (ref "P5") (pin "4") (pinfunction "4_4") (pintype "passive"))
      (node (ref "P5") (pin "8") (pinfunction "8_8") (pintype "passive"))
      (node (ref "P6") (pin "10") (pinfunction "10_10") (pintype "passive"))
      (node (ref "P6") (pin "12") (pinfunction "12_12") (pintype "passive"))
      (node (ref "P6") (pin "14") (pinfunction "14_14") (pintype "passive"))
      (node (ref "P6") (pin "16") (pinfunction "16_16") (pintype "passive"))
      (node (ref "P6") (pin "18") (pinfunction "18_18") (pintype "passive"))
      (node (ref "P6") (pin "2") (pinfunction "2_2") (pintype "passive"))
      (node (ref "P6") (pin "20") (pinfunction "20_20") (pintype "passive"))
      (node (ref "P6") (pin "4") (pinfunction "4_4") (pintype "passive"))
      (node (ref "P6") (pin "6") (pinfunction "6_6") (pintype "passive"))
      (node (ref "P6") (pin "8") (pinfunction "8_8") (pintype "passive"))
    )
    (net (code "184") (name "AGND4") (class "Default")
      (node (ref "P7") (pin "12") (pinfunction "12_12") (pintype "passive"))
      (node (ref "P7") (pin "16") (pinfunction "16_16") (pintype "passive"))
      (node (ref "P7") (pin "20") (pinfunction "20_20") (pintype "passive"))
      (node (ref "P7") (pin "24") (pinfunction "24_24") (pintype "passive"))
      (node (ref "P7") (pin "28") (pinfunction "28_28") (pintype "passive"))
      (node (ref "P7") (pin "32") (pinfunction "32_32") (pintype "passive"))
      (node (ref "P7") (pin "36") (pinfunction "36_36") (pintype "passive"))
      (node (ref "P7") (pin "4") (pinfunction "4_4") (pintype "passive"))
      (node (ref "P7") (pin "40") (pinfunction "40_40") (pintype "passive"))
      (node (ref "P7") (pin "44") (pinfunction "44_44") (pintype "passive"))
      (node (ref "P7") (pin "48") (pinfunction "48_48") (pintype "passive"))
      (node (ref "P7") (pin "8") (pinfunction "8_8") (pintype "passive"))
    )
    (net (code "185") (name "GND") (class "Default")
      (node (ref "C1") (pin "1") (pinfunction "1_1") (pintype "passive"))
      (node (ref "C2") (pin "1") (pinfunction "1_1") (pintype "passive"))
      (node (ref "C3") (pin "2") (pinfunction "2_2") (pintype "passive"))
      (node (ref "C4") (pin "2") (pinfunction "2_2") (pintype "passive"))
      (node (ref "C5") (pin "1") (pinfunction "1_1") (pintype "passive"))
      (node (ref "C6") (pin "1") (pinfunction "1_1") (pintype "passive"))
      (node (ref "C7") (pin "2") (pinfunction "2_2") (pintype "passive"))
      (node (ref "C8") (pin "2") (pinfunction "2_2") (pintype "passive"))
      (node (ref "MCP1") (pin "12") (pinfunction "A1_12") (pintype "passive"))
      (node (ref "MCP1") (pin "13") (pinfunction "A2_13") (pintype "passive"))
      (node (ref "MCP1") (pin "29") (pinfunction "PAD_29") (pintype "passive"))
      (node (ref "MCP1") (pin "6") (pinfunction "GND_6") (pintype "passive"))
      (node (ref "MCP2") (pin "11") (pinfunction "A0_11") (pintype "passive"))
      (node (ref "MCP2") (pin "12") (pinfunction "A1_12") (pintype "passive"))
      (node (ref "MCP2") (pin "13") (pinfunction "A2_13") (pintype "passive"))
      (node (ref "MCP2") (pin "29") (pinfunction "PAD_29") (pintype "passive"))
      (node (ref "MCP2") (pin "6") (pinfunction "GND_6") (pintype "passive"))
      (node (ref "ULN1") (pin "21") (pinfunction "PAD_21") (pintype "passive"))
      (node (ref "ULN1") (pin "8") (pinfunction "GND_8") (pintype "passive"))
      (node (ref "ULN2") (pin "21") (pinfunction "PAD_21") (pintype "passive"))
      (node (ref "ULN2") (pin "8") (pinfunction "GND_8") (pintype "passive"))
      (node (ref "ULN3") (pin "21") (pinfunction "PAD_21") (pintype "passive"))
      (node (ref "ULN3") (pin "8") (pinfunction "GND_8") (pintype "passive"))
      (node (ref "ULN4") (pin "21") (pinfunction "PAD_21") (pintype "passive"))
      (node (ref "ULN4") (pin "8") (pinfunction "GND_8") (pintype "passive"))
    )
    (net (code "186") (name "Net-(K2-Pad3)") (class "Default")
      (node (ref "K2") (pin "3") (pinfunction "3_3") (pintype "passive"))
      (node (ref "R11") (pin "2") (pintype "passive"))
      (node (ref "R12") (pin "1") (pintype "passive"))
      (node (ref "R3") (pin "1") (pintype "passive"))
    )
    (net (code "187") (name "Net-(K2-Pad6)") (class "Default")
      (node (ref "K2") (pin "6") (pinfunction "6_6") (pintype "passive"))
      (node (ref "R18") (pin "2") (pintype "passive"))
      (node (ref "R19") (pin "1") (pintype "passive"))
      (node (ref "R4") (pin "1") (pintype "passive"))
    )
    (net (code "188") (name "Net-(K3-Pad3)") (class "Default")
      (node (ref "K3") (pin "3") (pinfunction "3_3") (pintype "passive"))
      (node (ref "R12") (pin "2") (pintype "passive"))
      (node (ref "R13") (pin "1") (pintype "passive"))
      (node (ref "R5") (pin "1") (pintype "passive"))
    )
    (net (code "189") (name "Net-(K3-Pad6)") (class "Default")
      (node (ref "K3") (pin "6") (pinfunction "6_6") (pintype "passive"))
      (node (ref "R19") (pin "2") (pintype "passive"))
      (node (ref "R20") (pin "1") (pintype "passive"))
      (node (ref "R6") (pin "1") (pintype "passive"))
    )
    (net (code "190") (name "Net-(K4-Pad3)") (class "Default")
      (node (ref "K4") (pin "3") (pinfunction "3_3") (pintype "passive"))
      (node (ref "R13") (pin "2") (pintype "passive"))
      (node (ref "R14") (pin "1") (pintype "passive"))
      (node (ref "R7") (pin "1") (pintype "passive"))
    )
    (net (code "191") (name "Net-(K4-Pad6)") (class "Default")
      (node (ref "K4") (pin "6") (pinfunction "6_6") (pintype "passive"))
      (node (ref "R20") (pin "2") (pintype "passive"))
      (node (ref "R21") (pin "1") (pintype "passive"))
      (node (ref "R8") (pin "1") (pintype "passive"))
    )
    (net (code "192") (name "Net-(K5-Pad3)") (class "Default")
      (node (ref "K5") (pin "3") (pinfunction "3_3") (pintype "passive"))
      (node (ref "R14") (pin "2") (pintype "passive"))
      (node (ref "R15") (pin "1") (pintype "passive"))
    )
    (net (code "193") (name "Net-(K5-Pad6)") (class "Default")
      (node (ref "K5") (pin "6") (pinfunction "6_6") (pintype "passive"))
      (node (ref "R21") (pin "2") (pintype "passive"))
      (node (ref "R22") (pin "1") (pintype "passive"))
    )
    (net (code "194") (name "Net-(K6-Pad3)") (class "Default")
      (node (ref "K6") (pin "3") (pinfunction "3_3") (pintype "passive"))
      (node (ref "R15") (pin "2") (pintype "passive"))
      (node (ref "R16") (pin "1") (pintype "passive"))
    )
    (net (code "195") (name "Net-(K6-Pad6)") (class "Default")
      (node (ref "K6") (pin "6") (pinfunction "6_6") (pintype "passive"))
      (node (ref "R22") (pin "2") (pintype "passive"))
      (node (ref "R23") (pin "1") (pintype "passive"))
    )
    (net (code "196") (name "Net-(K7-Pad3)") (class "Default")
      (node (ref "K7") (pin "3") (pinfunction "3_3") (pintype "passive"))
      (node (ref "R16") (pin "2") (pintype "passive"))
      (node (ref "R17") (pin "1") (pintype "passive"))
    )
    (net (code "197") (name "Net-(K7-Pad6)") (class "Default")
      (node (ref "K7") (pin "6") (pinfunction "6_6") (pintype "passive"))
      (node (ref "R23") (pin "2") (pintype "passive"))
      (node (ref "R24") (pin "1") (pintype "passive"))
    )
    (net (code "198") (name "Net-(K8-Pad3)") (class "Default")
      (node (ref "K8") (pin "3") (pinfunction "3_3") (pintype "passive"))
      (node (ref "R17") (pin "2") (pintype "passive"))
      (node (ref "R9") (pin "1") (pintype "passive"))
    )
    (net (code "199") (name "Net-(K8-Pad6)") (class "Default")
      (node (ref "K8") (pin "6") (pinfunction "6_6") (pintype "passive"))
      (node (ref "R10") (pin "1") (pintype "passive"))
      (node (ref "R24") (pin "2") (pintype "passive"))
    )
    (net (code "200") (name "Net-(K10-Pad3)") (class "Default")
      (node (ref "K10") (pin "3") (pinfunction "3_3") (pintype "passive"))
      (node (ref "R29") (pin "1") (pintype "passive"))
      (node (ref "R37") (pin "2") (pintype "passive"))
      (node (ref "R38") (pin "1") (pintype "passive"))
    )
    (net (code "201") (name "Net-(K10-Pad6)") (class "Default")
      (node (ref "K10") (pin "6") (pinfunction "6_6") (pintype "passive"))
      (node (ref "R30") (pin "1") (pintype "passive"))
      (node (ref "R45") (pin "2") (pintype "passive"))
      (node (ref "R46") (pin "1") (pintype "passive"))
    )
    (net (code "202") (name "Net-(K11-Pad3)") (class "Default")
      (node (ref "K11") (pin "3") (pinfunction "3_3") (pintype "passive"))
      (node (ref "R31") (pin "1") (pintype "passive"))
      (node (ref "R38") (pin "2") (pintype "passive"))
      (node (ref "R39") (pin "1") (pintype "passive"))
    )
    (net (code "203") (name "Net-(K11-Pad6)") (class "Default")
      (node (ref "K11") (pin "6") (pinfunction "6_6") (pintype "passive"))
      (node (ref "R32") (pin "1") (pintype "passive"))
      (node (ref "R46") (pin "2") (pintype "passive"))
      (node (ref "R47") (pin "1") (pintype "passive"))
    )
    (net (code "204") (name "Net-(K12-Pad3)") (class "Default")
      (node (ref "K12") (pin "3") (pinfunction "3_3") (pintype "passive"))
      (node (ref "R33") (pin "1") (pintype "passive"))
      (node (ref "R39") (pin "2") (pintype "passive"))
      (node (ref "R40") (pin "1") (pintype "passive"))
    )
    (net (code "205") (name "Net-(K12-Pad6)") (class "Default")
      (node (ref "K12") (pin "6") (pinfunction "6_6") (pintype "passive"))
      (node (ref "R34") (pin "1") (pintype "passive"))
      (node (ref "R47") (pin "2") (pintype "passive"))
      (node (ref "R48") (pin "1") (pintype "passive"))
    )
    (net (code "206") (name "Net-(K13-Pad3)") (class "Default")
      (node (ref "K13") (pin "3") (pinfunction "3_3") (pintype "passive"))
      (node (ref "R40") (pin "2") (pintype "passive"))
      (node (ref "R41") (pin "1") (pintype "passive"))
    )
    (net (code "207") (name "Net-(K13-Pad6)") (class "Default")
      (node (ref "K13") (pin "6") (pinfunction "6_6") (pintype "passive"))
      (node (ref "R48") (pin "2") (pintype "passive"))
      (node (ref "R49") (pin "1") (pintype "passive"))
    )
    (net (code "208") (name "Net-(K14-Pad3)") (class "Default")
      (node (ref "K14") (pin "3") (pinfunction "3_3") (pintype "passive"))
      (node (ref "R41") (pin "2") (pintype "passive"))
      (node (ref "R42") (pin "1") (pintype "passive"))
    )
    (net (code "209") (name "Net-(K14-Pad6)") (class "Default")
      (node (ref "K14") (pin "6") (pinfunction "6_6") (pintype "passive"))
      (node (ref "R49") (pin "2") (pintype "passive"))
      (node (ref "R50") (pin "1") (pintype "passive"))
    )
    (net (code "210") (name "Net-(K15-Pad3)") (class "Default")
      (node (ref "K15") (pin "3") (pinfunction "3_3") (pintype "passive"))
      (node (ref "R42") (pin "2") (pintype "passive"))
      (node (ref "R43") (pin "1") (pintype "passive"))
    )
    (net (code "211") (name "Net-(K15-Pad6)") (class "Default")
      (node (ref "K15") (pin "6") (pinfunction "6_6") (pintype "passive"))
      (node (ref "R50") (pin "2") (pintype "passive"))
      (node (ref "R51") (pin "1") (pintype "passive"))
    )
    (net (code "212") (name "Net-(K17-Pad3)") (class "Default")
      (node (ref "K17") (pin "3") (pinfunction "3_3") (pintype "passive"))
      (node (ref "R55") (pin "1") (pintype "passive"))
      (node (ref "R65") (pin "1") (pintype "passive"))
    )
    (net (code "213") (name "Net-(K17-Pad6)") (class "Default")
      (node (ref "K17") (pin "6") (pinfunction "6_6") (pintype "passive"))
      (node (ref "R56") (pin "1") (pintype "passive"))
      (node (ref "R72") (pin "1") (pintype "passive"))
    )
    (net (code "214") (name "Net-(K18-Pad3)") (class "Default")
      (node (ref "K18") (pin "3") (pinfunction "3_3") (pintype "passive"))
      (node (ref "R57") (pin "1") (pintype "passive"))
      (node (ref "R65") (pin "2") (pintype "passive"))
      (node (ref "R66") (pin "1") (pintype "passive"))
    )
    (net (code "215") (name "Net-(K18-Pad6)") (class "Default")
      (node (ref "K18") (pin "6") (pinfunction "6_6") (pintype "passive"))
      (node (ref "R58") (pin "1") (pintype "passive"))
      (node (ref "R72") (pin "2") (pintype "passive"))
      (node (ref "R73") (pin "1") (pintype "passive"))
    )
    (net (code "216") (name "Net-(K19-Pad3)") (class "Default")
      (node (ref "K19") (pin "3") (pinfunction "3_3") (pintype "passive"))
      (node (ref "R59") (pin "1") (pintype "passive"))
      (node (ref "R66") (pin "2") (pintype "passive"))
      (node (ref "R67") (pin "1") (pintype "passive"))
    )
    (net (code "217") (name "Net-(K19-Pad6)") (class "Default")
      (node (ref "K19") (pin "6") (pinfunction "6_6") (pintype "passive"))
      (node (ref "R60") (pin "1") (pintype "passive"))
      (node (ref "R73") (pin "2") (pintype "passive"))
      (node (ref "R74") (pin "1") (pintype "passive"))
    )
    (net (code "218") (name "Net-(K20-Pad3)") (class "Default")
      (node (ref "K20") (pin "3") (pinfunction "3_3") (pintype "passive"))
      (node (ref "R61") (pin "1") (pintype "passive"))
      (node (ref "R67") (pin "2") (pintype "passive"))
      (node (ref "R68") (pin "1") (pintype "passive"))
    )
    (net (code "219") (name "Net-(K20-Pad6)") (class "Default")
      (node (ref "K20") (pin "6") (pinfunction "6_6") (pintype "passive"))
      (node (ref "R62") (pin "1") (pintype "passive"))
      (node (ref "R74") (pin "2") (pintype "passive"))
      (node (ref "R75") (pin "1") (pintype "passive"))
    )
    (net (code "220") (name "Net-(K21-Pad3)") (class "Default")
      (node (ref "K21") (pin "3") (pinfunction "3_3") (pintype "passive"))
      (node (ref "R68") (pin "2") (pintype "passive"))
      (node (ref "R69") (pin "1") (pintype "passive"))
    )
    (net (code "221") (name "Net-(K21-Pad6)") (class "Default")
      (node (ref "K21") (pin "6") (pinfunction "6_6") (pintype "passive"))
      (node (ref "R75") (pin "2") (pintype "passive"))
      (node (ref "R76") (pin "1") (pintype "passive"))
    )
    (net (code "222") (name "Net-(K22-Pad3)") (class "Default")
      (node (ref "K22") (pin "3") (pinfunction "3_3") (pintype "passive"))
      (node (ref "R69") (pin "2") (pintype "passive"))
      (node (ref "R70") (pin "1") (pintype "passive"))
    )
    (net (code "223") (name "Net-(K22-Pad6)") (class "Default")
      (node (ref "K22") (pin "6") (pinfunction "6_6") (pintype "passive"))
      (node (ref "R76") (pin "2") (pintype "passive"))
      (node (ref "R77") (pin "1") (pintype "passive"))
    )
    (net (code "224") (name "Net-(K23-Pad3)") (class "Default")
      (node (ref "K23") (pin "3") (pinfunction "3_3") (pintype "passive"))
      (node (ref "R70") (pin "2") (pintype "passive"))
      (node (ref "R71") (pin "1") (pintype "passive"))
    )
    (net (code "225") (name "Net-(K23-Pad6)") (class "Default")
      (node (ref "K23") (pin "6") (pinfunction "6_6") (pintype "passive"))
      (node (ref "R77") (pin "2") (pintype "passive"))
      (node (ref "R78") (pin "1") (pintype "passive"))
    )
    (net (code "226") (name "Net-(MCP1-GPA0)") (class "Default")
      (node (ref "MCP1") (pin "17") (pinfunction "GPA0_17") (pintype "passive"))
      (node (ref "ULN1") (pin "6") (pinfunction "B8_6") (pintype "passive"))
    )
    (net (code "227") (name "Net-(MCP1-GPA1)") (class "Default")
      (node (ref "MCP1") (pin "18") (pinfunction "GPA1_18") (pintype "passive"))
      (node (ref "ULN1") (pin "5") (pinfunction "B7_5") (pintype "passive"))
    )
    (net (code "228") (name "Net-(MCP1-GPA2)") (class "Default")
      (node (ref "MCP1") (pin "19") (pinfunction "GPA2_19") (pintype "passive"))
      (node (ref "ULN1") (pin "4") (pinfunction "B6_4") (pintype "passive"))
    )
    (net (code "229") (name "Net-(MCP1-GPA3)") (class "Default")
      (node (ref "MCP1") (pin "20") (pinfunction "GPA3_20") (pintype "passive"))
      (node (ref "ULN1") (pin "3") (pinfunction "B5_3") (pintype "passive"))
    )
    (net (code "230") (name "Net-(MCP1-GPA4)") (class "Default")
      (node (ref "MCP1") (pin "21") (pinfunction "GPA4_21") (pintype "passive"))
      (node (ref "ULN1") (pin "2") (pinfunction "B4_2") (pintype "passive"))
    )
    (net (code "231") (name "Net-(MCP1-GPA5)") (class "Default")
      (node (ref "MCP1") (pin "22") (pinfunction "GPA5_22") (pintype "passive"))
      (node (ref "ULN1") (pin "1") (pinfunction "B3_1") (pintype "passive"))
    )
    (net (code "232") (name "Net-(MCP1-GPA6)") (class "Default")
      (node (ref "MCP1") (pin "23") (pinfunction "GPA6_23") (pintype "passive"))
      (node (ref "ULN1") (pin "20") (pinfunction "B2_20") (pintype "passive"))
    )
    (net (code "233") (name "Net-(MCP1-GPA7)") (class "Default")
      (node (ref "MCP1") (pin "24") (pinfunction "GPA7_24") (pintype "passive"))
      (node (ref "ULN1") (pin "19") (pinfunction "B1_19") (pintype "passive"))
    )
    (net (code "234") (name "Net-(MCP1-GPB0)") (class "Default")
      (node (ref "MCP1") (pin "25") (pinfunction "GPB0_25") (pintype "passive"))
      (node (ref "ULN2") (pin "6") (pinfunction "B8_6") (pintype "passive"))
    )
    (net (code "235") (name "Net-(MCP1-GPB1)") (class "Default")
      (node (ref "MCP1") (pin "26") (pinfunction "GPB1_26") (pintype "passive"))
      (node (ref "ULN2") (pin "5") (pinfunction "B7_5") (pintype "passive"))
    )
    (net (code "236") (name "Net-(MCP1-GPB2)") (class "Default")
      (node (ref "MCP1") (pin "27") (pinfunction "GPB2_27") (pintype "passive"))
      (node (ref "ULN2") (pin "4") (pinfunction "B6_4") (pintype "passive"))
    )
    (net (code "237") (name "Net-(MCP1-GPB3)") (class "Default")
      (node (ref "MCP1") (pin "28") (pinfunction "GPB3_28") (pintype "passive"))
      (node (ref "ULN2") (pin "3") (pinfunction "B5_3") (pintype "passive"))
    )
    (net (code "238") (name "Net-(MCP1-GPB4)") (class "Default")
      (node (ref "MCP1") (pin "1") (pinfunction "GPB4_1") (pintype "passive"))
      (node (ref "ULN2") (pin "2") (pinfunction "B4_2") (pintype "passive"))
    )
    (net (code "239") (name "Net-(MCP1-GPB5)") (class "Default")
      (node (ref "MCP1") (pin "2") (pinfunction "GPB5_2") (pintype "passive"))
      (node (ref "ULN2") (pin "1") (pinfunction "B3_1") (pintype "passive"))
    )
    (net (code "240") (name "Net-(MCP1-GPB6)") (class "Default")
      (node (ref "MCP1") (pin "3") (pinfunction "GPB6_3") (pintype "passive"))
      (node (ref "ULN2") (pin "20") (pinfunction "B2_20") (pintype "passive"))
    )
    (net (code "241") (name "Net-(MCP1-GPB7)") (class "Default")
      (node (ref "MCP1") (pin "4") (pinfunction "GPB7_4") (pintype "passive"))
      (node (ref "ULN2") (pin "19") (pinfunction "B1_19") (pintype "passive"))
    )
    (net (code "242") (name "Net-(MCP1-~{RESET})") (class "Default")
      (node (ref "C2") (pin "2") (pinfunction "2_2") (pintype "passive"))
      (node (ref "MCP1") (pin "14") (pinfunction "~{RESET}_14") (pintype "passive"))
      (node (ref "R44") (pin "2") (pintype "passive"))
    )
    (net (code "243") (name "Net-(MCP2-GPA0)") (class "Default")
      (node (ref "MCP2") (pin "17") (pinfunction "GPA0_17") (pintype "passive"))
      (node (ref "ULN3") (pin "6") (pinfunction "B8_6") (pintype "passive"))
    )
    (net (code "244") (name "Net-(MCP2-GPA1)") (class "Default")
      (node (ref "MCP2") (pin "18") (pinfunction "GPA1_18") (pintype "passive"))
      (node (ref "ULN3") (pin "5") (pinfunction "B7_5") (pintype "passive"))
    )
    (net (code "245") (name "Net-(MCP2-GPA2)") (class "Default")
      (node (ref "MCP2") (pin "19") (pinfunction "GPA2_19") (pintype "passive"))
      (node (ref "ULN3") (pin "4") (pinfunction "B6_4") (pintype "passive"))
    )
    (net (code "246") (name "Net-(MCP2-GPA3)") (class "Default")
      (node (ref "MCP2") (pin "20") (pinfunction "GPA3_20") (pintype "passive"))
      (node (ref "ULN3") (pin "3") (pinfunction "B5_3") (pintype "passive"))
    )
    (net (code "247") (name "Net-(MCP2-GPA4)") (class "Default")
      (node (ref "MCP2") (pin "21") (pinfunction "GPA4_21") (pintype "passive"))
      (node (ref "ULN3") (pin "2") (pinfunction "B4_2") (pintype "passive"))
    )
    (net (code "248") (name "Net-(MCP2-GPA5)") (class "Default")
      (node (ref "MCP2") (pin "22") (pinfunction "GPA5_22") (pintype "passive"))
      (node (ref "ULN3") (pin "1") (pinfunction "B3_1") (pintype "passive"))
    )
    (net (code "249") (name "Net-(MCP2-GPA6)") (class "Default")
      (node (ref "MCP2") (pin "23") (pinfunction "GPA6_23") (pintype "passive"))
      (node (ref "ULN3") (pin "20") (pinfunction "B2_20") (pintype "passive"))
    )
    (net (code "250") (name "Net-(MCP2-GPA7)") (class "Default")
      (node (ref "MCP2") (pin "24") (pinfunction "GPA7_24") (pintype "passive"))
      (node (ref "ULN3") (pin "19") (pinfunction "B1_19") (pintype "passive"))
    )
    (net (code "251") (name "Net-(MCP2-GPB0)") (class "Default")
      (node (ref "MCP2") (pin "25") (pinfunction "GPB0_25") (pintype "passive"))
      (node (ref "ULN4") (pin "6") (pinfunction "B8_6") (pintype "passive"))
    )
    (net (code "252") (name "Net-(MCP2-GPB1)") (class "Default")
      (node (ref "MCP2") (pin "26") (pinfunction "GPB1_26") (pintype "passive"))
      (node (ref "ULN4") (pin "5") (pinfunction "B7_5") (pintype "passive"))
    )
    (net (code "253") (name "Net-(MCP2-GPB2)") (class "Default")
      (node (ref "MCP2") (pin "27") (pinfunction "GPB2_27") (pintype "passive"))
      (node (ref "ULN4") (pin "4") (pinfunction "B6_4") (pintype "passive"))
    )
    (net (code "254") (name "Net-(MCP2-GPB3)") (class "Default")
      (node (ref "MCP2") (pin "28") (pinfunction "GPB3_28") (pintype "passive"))
      (node (ref "ULN4") (pin "3") (pinfunction "B5_3") (pintype "passive"))
    )
    (net (code "255") (name "Net-(MCP2-GPB4)") (class "Default")
      (node (ref "MCP2") (pin "1") (pinfunction "GPB4_1") (pintype "passive"))
      (node (ref "ULN4") (pin "2") (pinfunction "B4_2") (pintype "passive"))
    )
    (net (code "256") (name "Net-(MCP2-GPB5)") (class "Default")
      (node (ref "MCP2") (pin "2") (pinfunction "GPB5_2") (pintype "passive"))
      (node (ref "ULN4") (pin "1") (pinfunction "B3_1") (pintype "passive"))
    )
    (net (code "257") (name "Net-(MCP2-GPB6)") (class "Default")
      (node (ref "MCP2") (pin "3") (pinfunction "GPB6_3") (pintype "passive"))
      (node (ref "ULN4") (pin "20") (pinfunction "B2_20") (pintype "passive"))
    )
    (net (code "258") (name "Net-(MCP2-GPB7)") (class "Default")
      (node (ref "MCP2") (pin "4") (pinfunction "GPB7_4") (pintype "passive"))
      (node (ref "ULN4") (pin "19") (pinfunction "B1_19") (pintype "passive"))
    )
    (net (code "259") (name "Net-(MCP2-~{RESET})") (class "Default")
      (node (ref "C6") (pin "2") (pinfunction "2_2") (pintype "passive"))
      (node (ref "MCP2") (pin "14") (pinfunction "~{RESET}_14") (pintype "passive"))
      (node (ref "R54") (pin "2") (pintype "passive"))
    )
    (net (code "260") (name "unconnected-(K5-Pad2)") (class "Default")
      (node (ref "K5") (pin "2") (pinfunction "2_2") (pintype "passive+no_connect"))
    )
    (net (code "261") (name "unconnected-(K5-Pad7)") (class "Default")
      (node (ref "K5") (pin "7") (pinfunction "7_7") (pintype "passive+no_connect"))
    )
    (net (code "262") (name "unconnected-(K6-Pad2)") (class "Default")
      (node (ref "K6") (pin "2") (pinfunction "2_2") (pintype "passive+no_connect"))
    )
    (net (code "263") (name "unconnected-(K6-Pad7)") (class "Default")
      (node (ref "K6") (pin "7") (pinfunction "7_7") (pintype "passive+no_connect"))
    )
    (net (code "264") (name "unconnected-(K7-Pad2)") (class "Default")
      (node (ref "K7") (pin "2") (pinfunction "2_2") (pintype "passive+no_connect"))
    )
    (net (code "265") (name "unconnected-(K7-Pad7)") (class "Default")
      (node (ref "K7") (pin "7") (pinfunction "7_7") (pintype "passive+no_connect"))
    )
    (net (code "266") (name "unconnected-(K8-Pad2)") (class "Default")
      (node (ref "K8") (pin "2") (pinfunction "2_2") (pintype "passive+no_connect"))
    )
    (net (code "267") (name "unconnected-(K8-Pad7)") (class "Default")
      (node (ref "K8") (pin "7") (pinfunction "7_7") (pintype "passive+no_connect"))
    )
    (net (code "268") (name "unconnected-(K13-Pad2)") (class "Default")
      (node (ref "K13") (pin "2") (pinfunction "2_2") (pintype "passive+no_connect"))
    )
    (net (code "269") (name "unconnected-(K13-Pad7)") (class "Default")
      (node (ref "K13") (pin "7") (pinfunction "7_7") (pintype "passive+no_connect"))
    )
    (net (code "270") (name "unconnected-(K14-Pad2)") (class "Default")
      (node (ref "K14") (pin "2") (pinfunction "2_2") (pintype "passive+no_connect"))
    )
    (net (code "271") (name "unconnected-(K14-Pad7)") (class "Default")
      (node (ref "K14") (pin "7") (pinfunction "7_7") (pintype "passive+no_connect"))
    )
    (net (code "272") (name "unconnected-(K15-Pad2)") (class "Default")
      (node (ref "K15") (pin "2") (pinfunction "2_2") (pintype "passive+no_connect"))
    )
    (net (code "273") (name "unconnected-(K15-Pad7)") (class "Default")
      (node (ref "K15") (pin "7") (pinfunction "7_7") (pintype "passive+no_connect"))
    )
    (net (code "274") (name "unconnected-(K16-Pad2)") (class "Default")
      (node (ref "K16") (pin "2") (pinfunction "2_2") (pintype "passive+no_connect"))
    )
    (net (code "275") (name "unconnected-(K16-Pad7)") (class "Default")
      (node (ref "K16") (pin "7") (pinfunction "7_7") (pintype "passive+no_connect"))
    )
    (net (code "276") (name "unconnected-(K21-Pad2)") (class "Default")
      (node (ref "K21") (pin "2") (pinfunction "2_2") (pintype "passive+no_connect"))
    )
    (net (code "277") (name "unconnected-(K21-Pad7)") (class "Default")
      (node (ref "K21") (pin "7") (pinfunction "7_7") (pintype "passive+no_connect"))
    )
    (net (code "278") (name "unconnected-(K22-Pad2)") (class "Default")
      (node (ref "K22") (pin "2") (pinfunction "2_2") (pintype "passive+no_connect"))
    )
    (net (code "279") (name "unconnected-(K22-Pad7)") (class "Default")
      (node (ref "K22") (pin "7") (pinfunction "7_7") (pintype "passive+no_connect"))
    )
    (net (code "280") (name "unconnected-(K23-Pad2)") (class "Default")
      (node (ref "K23") (pin "2") (pinfunction "2_2") (pintype "passive+no_connect"))
    )
    (net (code "281") (name "unconnected-(K23-Pad7)") (class "Default")
      (node (ref "K23") (pin "7") (pinfunction "7_7") (pintype "passive+no_connect"))
    )
    (net (code "282") (name "unconnected-(K24-Pad2)") (class "Default")
      (node (ref "K24") (pin "2") (pinfunction "2_2") (pintype "passive+no_connect"))
    )
    (net (code "283") (name "unconnected-(K24-Pad7)") (class "Default")
      (node (ref "K24") (pin "7") (pinfunction "7_7") (pintype "passive+no_connect"))
    )
    (net (code "284") (name "unconnected-(MCP1-INTA-Pad16)") (class "Default")
      (node (ref "MCP1") (pin "16") (pinfunction "INTA_16") (pintype "passive+no_connect"))
    )
    (net (code "285") (name "unconnected-(MCP1-INTB-Pad15)") (class "Default")
      (node (ref "MCP1") (pin "15") (pinfunction "INTB_15") (pintype "passive+no_connect"))
    )
    (net (code "286") (name "unconnected-(MCP2-INTA-Pad16)") (class "Default")
      (node (ref "MCP2") (pin "16") (pinfunction "INTA_16") (pintype "passive+no_connect"))
    )
    (net (code "287") (name "unconnected-(MCP2-INTB-Pad15)") (class "Default")
      (node (ref "MCP2") (pin "15") (pinfunction "INTB_15") (pintype "passive+no_connect"))
    )
    (net (code "288") (name "unconnected-(ULN4-C7-Pad11)") (class "Default")
      (node (ref "ULN4") (pin "11") (pinfunction "C7_11") (pintype "passive"))
    )
    (net (code "289") (name "unconnected-(ULN4-C8-Pad10)") (class "Default")
      (node (ref "ULN4") (pin "10") (pinfunction "C8_10") (pintype "passive"))
    )
  )
)
